# Breadboard.net
KiCad netlist of a schematic drawn in EAGLE
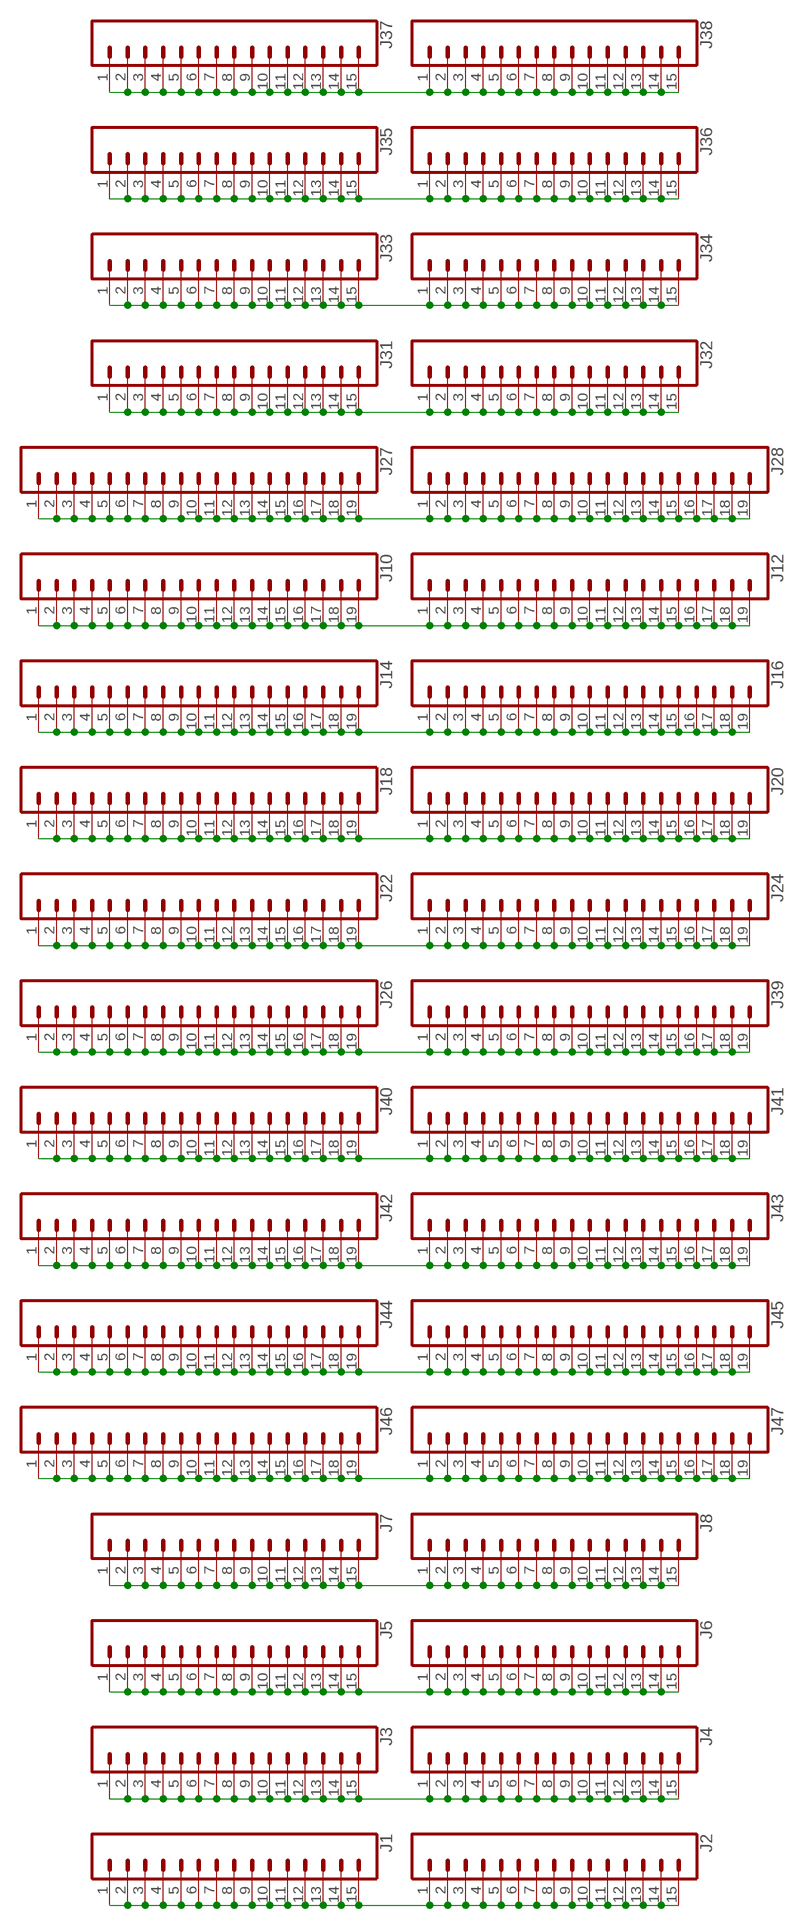
[diagram p0: schematic, sheet 1]
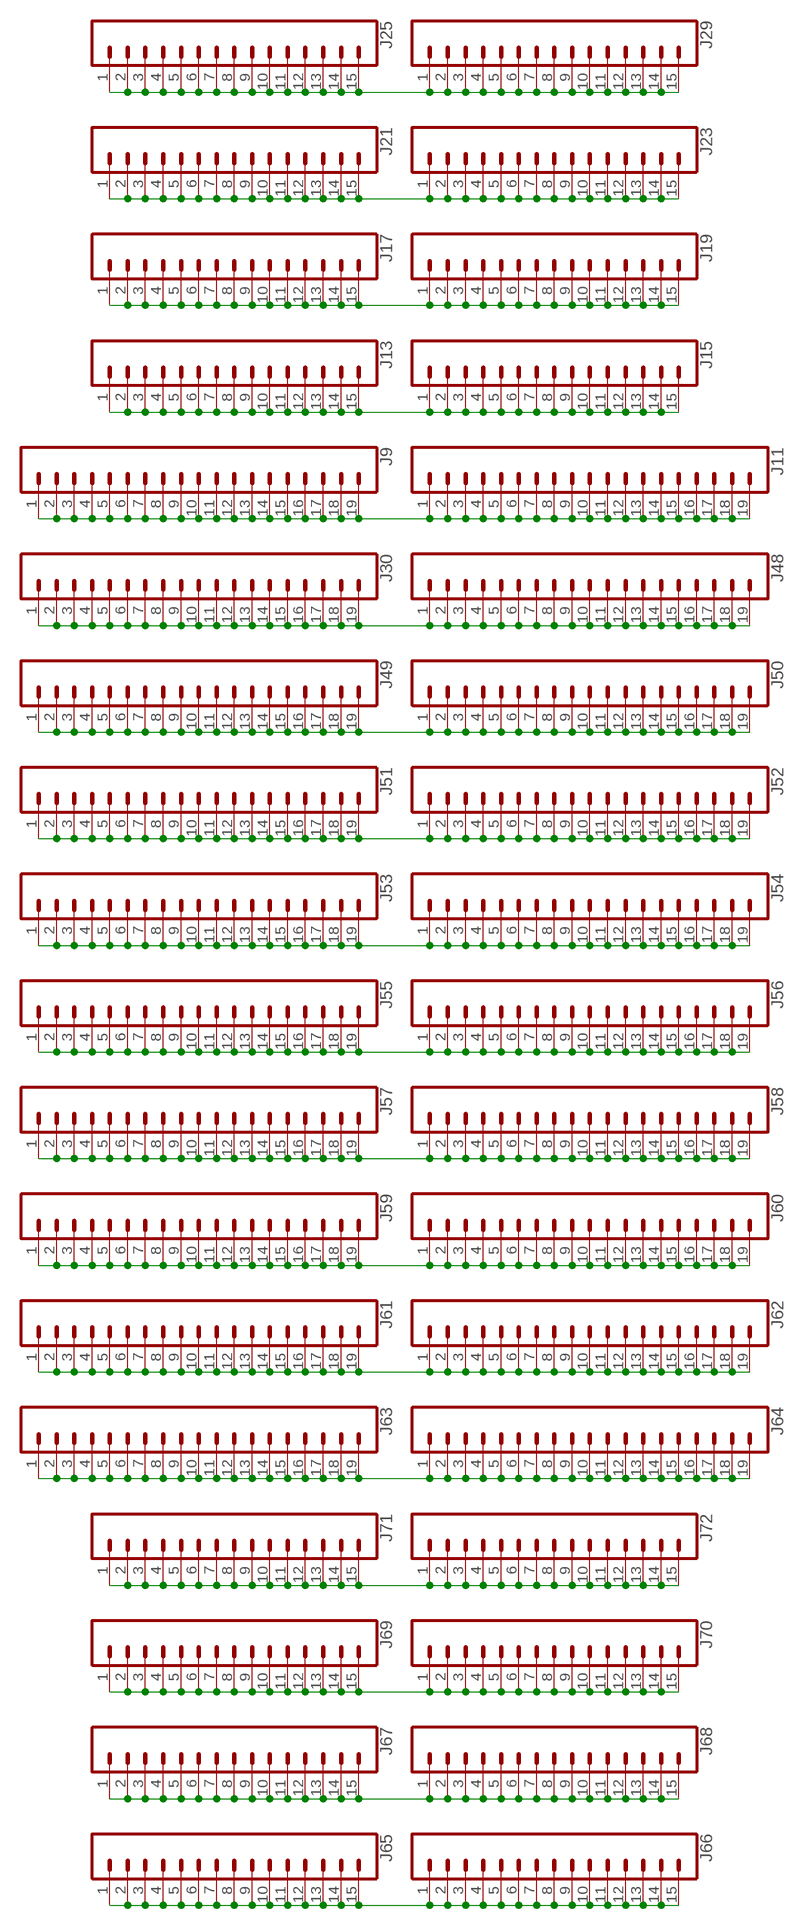
[diagram p1: schematic, sheet 2]

(export (version "E")
  (design (tool "Eeschema 10.0.6"))
  (components
    (comp (ref "J1")
      (value "CONN_15")
      (footprint "eagle-import:1X15")
      (libsource (lib "eagle-import") (part "CONN_15"))
    )
    (comp (ref "J2")
      (value "CONN_15")
      (footprint "eagle-import:1X15")
      (libsource (lib "eagle-import") (part "CONN_15"))
    )
    (comp (ref "J3")
      (value "CONN_15")
      (footprint "eagle-import:1X15")
      (libsource (lib "eagle-import") (part "CONN_15"))
    )
    (comp (ref "J4")
      (value "CONN_15")
      (footprint "eagle-import:1X15")
      (libsource (lib "eagle-import") (part "CONN_15"))
    )
    (comp (ref "J5")
      (value "CONN_15")
      (footprint "eagle-import:1X15")
      (libsource (lib "eagle-import") (part "CONN_15"))
    )
    (comp (ref "J6")
      (value "CONN_15")
      (footprint "eagle-import:1X15")
      (libsource (lib "eagle-import") (part "CONN_15"))
    )
    (comp (ref "J7")
      (value "CONN_15")
      (footprint "eagle-import:1X15")
      (libsource (lib "eagle-import") (part "CONN_15"))
    )
    (comp (ref "J8")
      (value "CONN_15")
      (footprint "eagle-import:1X15")
      (libsource (lib "eagle-import") (part "CONN_15"))
    )
    (comp (ref "J10")
      (value "CONN_19")
      (footprint "eagle-import:1X19")
      (libsource (lib "eagle-import") (part "CONN_19"))
    )
    (comp (ref "J12")
      (value "CONN_19")
      (footprint "eagle-import:1X19")
      (libsource (lib "eagle-import") (part "CONN_19"))
    )
    (comp (ref "J14")
      (value "CONN_19")
      (footprint "eagle-import:1X19")
      (libsource (lib "eagle-import") (part "CONN_19"))
    )
    (comp (ref "J16")
      (value "CONN_19")
      (footprint "eagle-import:1X19")
      (libsource (lib "eagle-import") (part "CONN_19"))
    )
    (comp (ref "J18")
      (value "CONN_19")
      (footprint "eagle-import:1X19")
      (libsource (lib "eagle-import") (part "CONN_19"))
    )
    (comp (ref "J20")
      (value "CONN_19")
      (footprint "eagle-import:1X19")
      (libsource (lib "eagle-import") (part "CONN_19"))
    )
    (comp (ref "J22")
      (value "CONN_19")
      (footprint "eagle-import:1X19")
      (libsource (lib "eagle-import") (part "CONN_19"))
    )
    (comp (ref "J24")
      (value "CONN_19")
      (footprint "eagle-import:1X19")
      (libsource (lib "eagle-import") (part "CONN_19"))
    )
    (comp (ref "J26")
      (value "CONN_19")
      (footprint "eagle-import:1X19")
      (libsource (lib "eagle-import") (part "CONN_19"))
    )
    (comp (ref "J27")
      (value "CONN_19")
      (footprint "eagle-import:1X19")
      (libsource (lib "eagle-import") (part "CONN_19"))
    )
    (comp (ref "J28")
      (value "CONN_19")
      (footprint "eagle-import:1X19")
      (libsource (lib "eagle-import") (part "CONN_19"))
    )
    (comp (ref "J31")
      (value "CONN_15")
      (footprint "eagle-import:1X15")
      (libsource (lib "eagle-import") (part "CONN_15"))
    )
    (comp (ref "J32")
      (value "CONN_15")
      (footprint "eagle-import:1X15")
      (libsource (lib "eagle-import") (part "CONN_15"))
    )
    (comp (ref "J33")
      (value "CONN_15")
      (footprint "eagle-import:1X15")
      (libsource (lib "eagle-import") (part "CONN_15"))
    )
    (comp (ref "J34")
      (value "CONN_15")
      (footprint "eagle-import:1X15")
      (libsource (lib "eagle-import") (part "CONN_15"))
    )
    (comp (ref "J35")
      (value "CONN_15")
      (footprint "eagle-import:1X15")
      (libsource (lib "eagle-import") (part "CONN_15"))
    )
    (comp (ref "J36")
      (value "CONN_15")
      (footprint "eagle-import:1X15")
      (libsource (lib "eagle-import") (part "CONN_15"))
    )
    (comp (ref "J37")
      (value "CONN_15")
      (footprint "eagle-import:1X15")
      (libsource (lib "eagle-import") (part "CONN_15"))
    )
    (comp (ref "J38")
      (value "CONN_15")
      (footprint "eagle-import:1X15")
      (libsource (lib "eagle-import") (part "CONN_15"))
    )
    (comp (ref "J39")
      (value "CONN_19")
      (footprint "eagle-import:1X19")
      (libsource (lib "eagle-import") (part "CONN_19"))
    )
    (comp (ref "J40")
      (value "CONN_19")
      (footprint "eagle-import:1X19")
      (libsource (lib "eagle-import") (part "CONN_19"))
    )
    (comp (ref "J41")
      (value "CONN_19")
      (footprint "eagle-import:1X19")
      (libsource (lib "eagle-import") (part "CONN_19"))
    )
    (comp (ref "J42")
      (value "CONN_19")
      (footprint "eagle-import:1X19")
      (libsource (lib "eagle-import") (part "CONN_19"))
    )
    (comp (ref "J43")
      (value "CONN_19")
      (footprint "eagle-import:1X19")
      (libsource (lib "eagle-import") (part "CONN_19"))
    )
    (comp (ref "J44")
      (value "CONN_19")
      (footprint "eagle-import:1X19")
      (libsource (lib "eagle-import") (part "CONN_19"))
    )
    (comp (ref "J45")
      (value "CONN_19")
      (footprint "eagle-import:1X19")
      (libsource (lib "eagle-import") (part "CONN_19"))
    )
    (comp (ref "J46")
      (value "CONN_19")
      (footprint "eagle-import:1X19")
      (libsource (lib "eagle-import") (part "CONN_19"))
    )
    (comp (ref "J47")
      (value "CONN_19")
      (footprint "eagle-import:1X19")
      (libsource (lib "eagle-import") (part "CONN_19"))
    )
    (comp (ref "J9")
      (value "CONN_19")
      (footprint "eagle-import:1X19")
      (libsource (lib "eagle-import") (part "CONN_19"))
    )
    (comp (ref "J11")
      (value "CONN_19")
      (footprint "eagle-import:1X19")
      (libsource (lib "eagle-import") (part "CONN_19"))
    )
    (comp (ref "J13")
      (value "CONN_15")
      (footprint "eagle-import:1X15")
      (libsource (lib "eagle-import") (part "CONN_15"))
    )
    (comp (ref "J15")
      (value "CONN_15")
      (footprint "eagle-import:1X15")
      (libsource (lib "eagle-import") (part "CONN_15"))
    )
    (comp (ref "J17")
      (value "CONN_15")
      (footprint "eagle-import:1X15")
      (libsource (lib "eagle-import") (part "CONN_15"))
    )
    (comp (ref "J19")
      (value "CONN_15")
      (footprint "eagle-import:1X15")
      (libsource (lib "eagle-import") (part "CONN_15"))
    )
    (comp (ref "J21")
      (value "CONN_15")
      (footprint "eagle-import:1X15")
      (libsource (lib "eagle-import") (part "CONN_15"))
    )
    (comp (ref "J23")
      (value "CONN_15")
      (footprint "eagle-import:1X15")
      (libsource (lib "eagle-import") (part "CONN_15"))
    )
    (comp (ref "J25")
      (value "CONN_15")
      (footprint "eagle-import:1X15")
      (libsource (lib "eagle-import") (part "CONN_15"))
    )
    (comp (ref "J29")
      (value "CONN_15")
      (footprint "eagle-import:1X15")
      (libsource (lib "eagle-import") (part "CONN_15"))
    )
    (comp (ref "J30")
      (value "CONN_19")
      (footprint "eagle-import:1X19")
      (libsource (lib "eagle-import") (part "CONN_19"))
    )
    (comp (ref "J48")
      (value "CONN_19")
      (footprint "eagle-import:1X19")
      (libsource (lib "eagle-import") (part "CONN_19"))
    )
    (comp (ref "J49")
      (value "CONN_19")
      (footprint "eagle-import:1X19")
      (libsource (lib "eagle-import") (part "CONN_19"))
    )
    (comp (ref "J50")
      (value "CONN_19")
      (footprint "eagle-import:1X19")
      (libsource (lib "eagle-import") (part "CONN_19"))
    )
    (comp (ref "J51")
      (value "CONN_19")
      (footprint "eagle-import:1X19")
      (libsource (lib "eagle-import") (part "CONN_19"))
    )
    (comp (ref "J52")
      (value "CONN_19")
      (footprint "eagle-import:1X19")
      (libsource (lib "eagle-import") (part "CONN_19"))
    )
    (comp (ref "J53")
      (value "CONN_19")
      (footprint "eagle-import:1X19")
      (libsource (lib "eagle-import") (part "CONN_19"))
    )
    (comp (ref "J54")
      (value "CONN_19")
      (footprint "eagle-import:1X19")
      (libsource (lib "eagle-import") (part "CONN_19"))
    )
    (comp (ref "J55")
      (value "CONN_19")
      (footprint "eagle-import:1X19")
      (libsource (lib "eagle-import") (part "CONN_19"))
    )
    (comp (ref "J56")
      (value "CONN_19")
      (footprint "eagle-import:1X19")
      (libsource (lib "eagle-import") (part "CONN_19"))
    )
    (comp (ref "J57")
      (value "CONN_19")
      (footprint "eagle-import:1X19")
      (libsource (lib "eagle-import") (part "CONN_19"))
    )
    (comp (ref "J58")
      (value "CONN_19")
      (footprint "eagle-import:1X19")
      (libsource (lib "eagle-import") (part "CONN_19"))
    )
    (comp (ref "J59")
      (value "CONN_19")
      (footprint "eagle-import:1X19")
      (libsource (lib "eagle-import") (part "CONN_19"))
    )
    (comp (ref "J60")
      (value "CONN_19")
      (footprint "eagle-import:1X19")
      (libsource (lib "eagle-import") (part "CONN_19"))
    )
    (comp (ref "J61")
      (value "CONN_19")
      (footprint "eagle-import:1X19")
      (libsource (lib "eagle-import") (part "CONN_19"))
    )
    (comp (ref "J62")
      (value "CONN_19")
      (footprint "eagle-import:1X19")
      (libsource (lib "eagle-import") (part "CONN_19"))
    )
    (comp (ref "J63")
      (value "CONN_19")
      (footprint "eagle-import:1X19")
      (libsource (lib "eagle-import") (part "CONN_19"))
    )
    (comp (ref "J64")
      (value "CONN_19")
      (footprint "eagle-import:1X19")
      (libsource (lib "eagle-import") (part "CONN_19"))
    )
    (comp (ref "J65")
      (value "CONN_15")
      (footprint "eagle-import:1X15")
      (libsource (lib "eagle-import") (part "CONN_15"))
    )
    (comp (ref "J66")
      (value "CONN_15")
      (footprint "eagle-import:1X15")
      (libsource (lib "eagle-import") (part "CONN_15"))
    )
    (comp (ref "J67")
      (value "CONN_15")
      (footprint "eagle-import:1X15")
      (libsource (lib "eagle-import") (part "CONN_15"))
    )
    (comp (ref "J68")
      (value "CONN_15")
      (footprint "eagle-import:1X15")
      (libsource (lib "eagle-import") (part "CONN_15"))
    )
    (comp (ref "J69")
      (value "CONN_15")
      (footprint "eagle-import:1X15")
      (libsource (lib "eagle-import") (part "CONN_15"))
    )
    (comp (ref "J70")
      (value "CONN_15")
      (footprint "eagle-import:1X15")
      (libsource (lib "eagle-import") (part "CONN_15"))
    )
    (comp (ref "J71")
      (value "CONN_15")
      (footprint "eagle-import:1X15")
      (libsource (lib "eagle-import") (part "CONN_15"))
    )
    (comp (ref "J72")
      (value "CONN_15")
      (footprint "eagle-import:1X15")
      (libsource (lib "eagle-import") (part "CONN_15"))
    )
  )
  (nets
    (net (code "1") (name "Net-(J1-Pad1)") (class "Default")
      (node (ref "J1") (pin "1") (pinfunction "1_1") (pintype "passive"))
      (node (ref "J1") (pin "10") (pinfunction "10_10") (pintype "passive"))
      (node (ref "J1") (pin "11") (pinfunction "11_11") (pintype "passive"))
      (node (ref "J1") (pin "12") (pinfunction "12_12") (pintype "passive"))
      (node (ref "J1") (pin "13") (pinfunction "13_13") (pintype "passive"))
      (node (ref "J1") (pin "14") (pinfunction "14_14") (pintype "passive"))
      (node (ref "J1") (pin "15") (pinfunction "15_15") (pintype "passive"))
      (node (ref "J1") (pin "2") (pinfunction "2_2") (pintype "passive"))
      (node (ref "J1") (pin "3") (pinfunction "3_3") (pintype "passive"))
      (node (ref "J1") (pin "4") (pinfunction "4_4") (pintype "passive"))
      (node (ref "J1") (pin "5") (pinfunction "5_5") (pintype "passive"))
      (node (ref "J1") (pin "6") (pinfunction "6_6") (pintype "passive"))
      (node (ref "J1") (pin "7") (pinfunction "7_7") (pintype "passive"))
      (node (ref "J1") (pin "8") (pinfunction "8_8") (pintype "passive"))
      (node (ref "J1") (pin "9") (pinfunction "9_9") (pintype "passive"))
      (node (ref "J2") (pin "1") (pinfunction "1_1") (pintype "passive"))
      (node (ref "J2") (pin "10") (pinfunction "10_10") (pintype "passive"))
      (node (ref "J2") (pin "11") (pinfunction "11_11") (pintype "passive"))
      (node (ref "J2") (pin "12") (pinfunction "12_12") (pintype "passive"))
      (node (ref "J2") (pin "13") (pinfunction "13_13") (pintype "passive"))
      (node (ref "J2") (pin "14") (pinfunction "14_14") (pintype "passive"))
      (node (ref "J2") (pin "15") (pinfunction "15_15") (pintype "passive"))
      (node (ref "J2") (pin "2") (pinfunction "2_2") (pintype "passive"))
      (node (ref "J2") (pin "3") (pinfunction "3_3") (pintype "passive"))
      (node (ref "J2") (pin "4") (pinfunction "4_4") (pintype "passive"))
      (node (ref "J2") (pin "5") (pinfunction "5_5") (pintype "passive"))
      (node (ref "J2") (pin "6") (pinfunction "6_6") (pintype "passive"))
      (node (ref "J2") (pin "7") (pinfunction "7_7") (pintype "passive"))
      (node (ref "J2") (pin "8") (pinfunction "8_8") (pintype "passive"))
      (node (ref "J2") (pin "9") (pinfunction "9_9") (pintype "passive"))
    )
    (net (code "2") (name "Net-(J3-Pad1)") (class "Default")
      (node (ref "J3") (pin "1") (pinfunction "1_1") (pintype "passive"))
      (node (ref "J3") (pin "10") (pinfunction "10_10") (pintype "passive"))
      (node (ref "J3") (pin "11") (pinfunction "11_11") (pintype "passive"))
      (node (ref "J3") (pin "12") (pinfunction "12_12") (pintype "passive"))
      (node (ref "J3") (pin "13") (pinfunction "13_13") (pintype "passive"))
      (node (ref "J3") (pin "14") (pinfunction "14_14") (pintype "passive"))
      (node (ref "J3") (pin "15") (pinfunction "15_15") (pintype "passive"))
      (node (ref "J3") (pin "2") (pinfunction "2_2") (pintype "passive"))
      (node (ref "J3") (pin "3") (pinfunction "3_3") (pintype "passive"))
      (node (ref "J3") (pin "4") (pinfunction "4_4") (pintype "passive"))
      (node (ref "J3") (pin "5") (pinfunction "5_5") (pintype "passive"))
      (node (ref "J3") (pin "6") (pinfunction "6_6") (pintype "passive"))
      (node (ref "J3") (pin "7") (pinfunction "7_7") (pintype "passive"))
      (node (ref "J3") (pin "8") (pinfunction "8_8") (pintype "passive"))
      (node (ref "J3") (pin "9") (pinfunction "9_9") (pintype "passive"))
      (node (ref "J4") (pin "1") (pinfunction "1_1") (pintype "passive"))
      (node (ref "J4") (pin "10") (pinfunction "10_10") (pintype "passive"))
      (node (ref "J4") (pin "11") (pinfunction "11_11") (pintype "passive"))
      (node (ref "J4") (pin "12") (pinfunction "12_12") (pintype "passive"))
      (node (ref "J4") (pin "13") (pinfunction "13_13") (pintype "passive"))
      (node (ref "J4") (pin "14") (pinfunction "14_14") (pintype "passive"))
      (node (ref "J4") (pin "15") (pinfunction "15_15") (pintype "passive"))
      (node (ref "J4") (pin "2") (pinfunction "2_2") (pintype "passive"))
      (node (ref "J4") (pin "3") (pinfunction "3_3") (pintype "passive"))
      (node (ref "J4") (pin "4") (pinfunction "4_4") (pintype "passive"))
      (node (ref "J4") (pin "5") (pinfunction "5_5") (pintype "passive"))
      (node (ref "J4") (pin "6") (pinfunction "6_6") (pintype "passive"))
      (node (ref "J4") (pin "7") (pinfunction "7_7") (pintype "passive"))
      (node (ref "J4") (pin "8") (pinfunction "8_8") (pintype "passive"))
      (node (ref "J4") (pin "9") (pinfunction "9_9") (pintype "passive"))
    )
    (net (code "3") (name "Net-(J5-Pad1)") (class "Default")
      (node (ref "J5") (pin "1") (pinfunction "1_1") (pintype "passive"))
      (node (ref "J5") (pin "10") (pinfunction "10_10") (pintype "passive"))
      (node (ref "J5") (pin "11") (pinfunction "11_11") (pintype "passive"))
      (node (ref "J5") (pin "12") (pinfunction "12_12") (pintype "passive"))
      (node (ref "J5") (pin "13") (pinfunction "13_13") (pintype "passive"))
      (node (ref "J5") (pin "14") (pinfunction "14_14") (pintype "passive"))
      (node (ref "J5") (pin "15") (pinfunction "15_15") (pintype "passive"))
      (node (ref "J5") (pin "2") (pinfunction "2_2") (pintype "passive"))
      (node (ref "J5") (pin "3") (pinfunction "3_3") (pintype "passive"))
      (node (ref "J5") (pin "4") (pinfunction "4_4") (pintype "passive"))
      (node (ref "J5") (pin "5") (pinfunction "5_5") (pintype "passive"))
      (node (ref "J5") (pin "6") (pinfunction "6_6") (pintype "passive"))
      (node (ref "J5") (pin "7") (pinfunction "7_7") (pintype "passive"))
      (node (ref "J5") (pin "8") (pinfunction "8_8") (pintype "passive"))
      (node (ref "J5") (pin "9") (pinfunction "9_9") (pintype "passive"))
      (node (ref "J6") (pin "1") (pinfunction "1_1") (pintype "passive"))
      (node (ref "J6") (pin "10") (pinfunction "10_10") (pintype "passive"))
      (node (ref "J6") (pin "11") (pinfunction "11_11") (pintype "passive"))
      (node (ref "J6") (pin "12") (pinfunction "12_12") (pintype "passive"))
      (node (ref "J6") (pin "13") (pinfunction "13_13") (pintype "passive"))
      (node (ref "J6") (pin "14") (pinfunction "14_14") (pintype "passive"))
      (node (ref "J6") (pin "15") (pinfunction "15_15") (pintype "passive"))
      (node (ref "J6") (pin "2") (pinfunction "2_2") (pintype "passive"))
      (node (ref "J6") (pin "3") (pinfunction "3_3") (pintype "passive"))
      (node (ref "J6") (pin "4") (pinfunction "4_4") (pintype "passive"))
      (node (ref "J6") (pin "5") (pinfunction "5_5") (pintype "passive"))
      (node (ref "J6") (pin "6") (pinfunction "6_6") (pintype "passive"))
      (node (ref "J6") (pin "7") (pinfunction "7_7") (pintype "passive"))
      (node (ref "J6") (pin "8") (pinfunction "8_8") (pintype "passive"))
      (node (ref "J6") (pin "9") (pinfunction "9_9") (pintype "passive"))
    )
    (net (code "4") (name "Net-(J7-Pad1)") (class "Default")
      (node (ref "J7") (pin "1") (pinfunction "1_1") (pintype "passive"))
      (node (ref "J7") (pin "10") (pinfunction "10_10") (pintype "passive"))
      (node (ref "J7") (pin "11") (pinfunction "11_11") (pintype "passive"))
      (node (ref "J7") (pin "12") (pinfunction "12_12") (pintype "passive"))
      (node (ref "J7") (pin "13") (pinfunction "13_13") (pintype "passive"))
      (node (ref "J7") (pin "14") (pinfunction "14_14") (pintype "passive"))
      (node (ref "J7") (pin "15") (pinfunction "15_15") (pintype "passive"))
      (node (ref "J7") (pin "2") (pinfunction "2_2") (pintype "passive"))
      (node (ref "J7") (pin "3") (pinfunction "3_3") (pintype "passive"))
      (node (ref "J7") (pin "4") (pinfunction "4_4") (pintype "passive"))
      (node (ref "J7") (pin "5") (pinfunction "5_5") (pintype "passive"))
      (node (ref "J7") (pin "6") (pinfunction "6_6") (pintype "passive"))
      (node (ref "J7") (pin "7") (pinfunction "7_7") (pintype "passive"))
      (node (ref "J7") (pin "8") (pinfunction "8_8") (pintype "passive"))
      (node (ref "J7") (pin "9") (pinfunction "9_9") (pintype "passive"))
      (node (ref "J8") (pin "1") (pinfunction "1_1") (pintype "passive"))
      (node (ref "J8") (pin "10") (pinfunction "10_10") (pintype "passive"))
      (node (ref "J8") (pin "11") (pinfunction "11_11") (pintype "passive"))
      (node (ref "J8") (pin "12") (pinfunction "12_12") (pintype "passive"))
      (node (ref "J8") (pin "13") (pinfunction "13_13") (pintype "passive"))
      (node (ref "J8") (pin "14") (pinfunction "14_14") (pintype "passive"))
      (node (ref "J8") (pin "15") (pinfunction "15_15") (pintype "passive"))
      (node (ref "J8") (pin "2") (pinfunction "2_2") (pintype "passive"))
      (node (ref "J8") (pin "3") (pinfunction "3_3") (pintype "passive"))
      (node (ref "J8") (pin "4") (pinfunction "4_4") (pintype "passive"))
      (node (ref "J8") (pin "5") (pinfunction "5_5") (pintype "passive"))
      (node (ref "J8") (pin "6") (pinfunction "6_6") (pintype "passive"))
      (node (ref "J8") (pin "7") (pinfunction "7_7") (pintype "passive"))
      (node (ref "J8") (pin "8") (pinfunction "8_8") (pintype "passive"))
      (node (ref "J8") (pin "9") (pinfunction "9_9") (pintype "passive"))
    )
    (net (code "5") (name "Net-(J10-Pad1)") (class "Default")
      (node (ref "J10") (pin "1") (pinfunction "1_1") (pintype "passive"))
      (node (ref "J10") (pin "10") (pinfunction "10_10") (pintype "passive"))
      (node (ref "J10") (pin "11") (pinfunction "11_11") (pintype "passive"))
      (node (ref "J10") (pin "12") (pinfunction "12_12") (pintype "passive"))
      (node (ref "J10") (pin "13") (pinfunction "13_13") (pintype "passive"))
      (node (ref "J10") (pin "14") (pinfunction "14_14") (pintype "passive"))
      (node (ref "J10") (pin "15") (pinfunction "15_15") (pintype "passive"))
      (node (ref "J10") (pin "16") (pinfunction "16_16") (pintype "passive"))
      (node (ref "J10") (pin "17") (pinfunction "17_17") (pintype "passive"))
      (node (ref "J10") (pin "18") (pinfunction "18_18") (pintype "passive"))
      (node (ref "J10") (pin "19") (pinfunction "19_19") (pintype "passive"))
      (node (ref "J10") (pin "2") (pinfunction "2_2") (pintype "passive"))
      (node (ref "J10") (pin "3") (pinfunction "3_3") (pintype "passive"))
      (node (ref "J10") (pin "4") (pinfunction "4_4") (pintype "passive"))
      (node (ref "J10") (pin "5") (pinfunction "5_5") (pintype "passive"))
      (node (ref "J10") (pin "6") (pinfunction "6_6") (pintype "passive"))
      (node (ref "J10") (pin "7") (pinfunction "7_7") (pintype "passive"))
      (node (ref "J10") (pin "8") (pinfunction "8_8") (pintype "passive"))
      (node (ref "J10") (pin "9") (pinfunction "9_9") (pintype "passive"))
      (node (ref "J12") (pin "1") (pinfunction "1_1") (pintype "passive"))
      (node (ref "J12") (pin "10") (pinfunction "10_10") (pintype "passive"))
      (node (ref "J12") (pin "11") (pinfunction "11_11") (pintype "passive"))
      (node (ref "J12") (pin "12") (pinfunction "12_12") (pintype "passive"))
      (node (ref "J12") (pin "13") (pinfunction "13_13") (pintype "passive"))
      (node (ref "J12") (pin "14") (pinfunction "14_14") (pintype "passive"))
      (node (ref "J12") (pin "15") (pinfunction "15_15") (pintype "passive"))
      (node (ref "J12") (pin "16") (pinfunction "16_16") (pintype "passive"))
      (node (ref "J12") (pin "17") (pinfunction "17_17") (pintype "passive"))
      (node (ref "J12") (pin "18") (pinfunction "18_18") (pintype "passive"))
      (node (ref "J12") (pin "19") (pinfunction "19_19") (pintype "passive"))
      (node (ref "J12") (pin "2") (pinfunction "2_2") (pintype "passive"))
      (node (ref "J12") (pin "3") (pinfunction "3_3") (pintype "passive"))
      (node (ref "J12") (pin "4") (pinfunction "4_4") (pintype "passive"))
      (node (ref "J12") (pin "5") (pinfunction "5_5") (pintype "passive"))
      (node (ref "J12") (pin "6") (pinfunction "6_6") (pintype "passive"))
      (node (ref "J12") (pin "7") (pinfunction "7_7") (pintype "passive"))
      (node (ref "J12") (pin "8") (pinfunction "8_8") (pintype "passive"))
      (node (ref "J12") (pin "9") (pinfunction "9_9") (pintype "passive"))
    )
    (net (code "6") (name "Net-(J11-Pad1)") (class "Default")
      (node (ref "J11") (pin "1") (pinfunction "1_1") (pintype "passive"))
      (node (ref "J11") (pin "10") (pinfunction "10_10") (pintype "passive"))
      (node (ref "J11") (pin "11") (pinfunction "11_11") (pintype "passive"))
      (node (ref "J11") (pin "12") (pinfunction "12_12") (pintype "passive"))
      (node (ref "J11") (pin "13") (pinfunction "13_13") (pintype "passive"))
      (node (ref "J11") (pin "14") (pinfunction "14_14") (pintype "passive"))
      (node (ref "J11") (pin "15") (pinfunction "15_15") (pintype "passive"))
      (node (ref "J11") (pin "16") (pinfunction "16_16") (pintype "passive"))
      (node (ref "J11") (pin "17") (pinfunction "17_17") (pintype "passive"))
      (node (ref "J11") (pin "18") (pinfunction "18_18") (pintype "passive"))
      (node (ref "J11") (pin "19") (pinfunction "19_19") (pintype "passive"))
      (node (ref "J11") (pin "2") (pinfunction "2_2") (pintype "passive"))
      (node (ref "J11") (pin "3") (pinfunction "3_3") (pintype "passive"))
      (node (ref "J11") (pin "4") (pinfunction "4_4") (pintype "passive"))
      (node (ref "J11") (pin "5") (pinfunction "5_5") (pintype "passive"))
      (node (ref "J11") (pin "6") (pinfunction "6_6") (pintype "passive"))
      (node (ref "J11") (pin "7") (pinfunction "7_7") (pintype "passive"))
      (node (ref "J11") (pin "8") (pinfunction "8_8") (pintype "passive"))
      (node (ref "J11") (pin "9") (pinfunction "9_9") (pintype "passive"))
      (node (ref "J9") (pin "1") (pinfunction "1_1") (pintype "passive"))
      (node (ref "J9") (pin "10") (pinfunction "10_10") (pintype "passive"))
      (node (ref "J9") (pin "11") (pinfunction "11_11") (pintype "passive"))
      (node (ref "J9") (pin "12") (pinfunction "12_12") (pintype "passive"))
      (node (ref "J9") (pin "13") (pinfunction "13_13") (pintype "passive"))
      (node (ref "J9") (pin "14") (pinfunction "14_14") (pintype "passive"))
      (node (ref "J9") (pin "15") (pinfunction "15_15") (pintype "passive"))
      (node (ref "J9") (pin "16") (pinfunction "16_16") (pintype "passive"))
      (node (ref "J9") (pin "17") (pinfunction "17_17") (pintype "passive"))
      (node (ref "J9") (pin "18") (pinfunction "18_18") (pintype "passive"))
      (node (ref "J9") (pin "19") (pinfunction "19_19") (pintype "passive"))
      (node (ref "J9") (pin "2") (pinfunction "2_2") (pintype "passive"))
      (node (ref "J9") (pin "3") (pinfunction "3_3") (pintype "passive"))
      (node (ref "J9") (pin "4") (pinfunction "4_4") (pintype "passive"))
      (node (ref "J9") (pin "5") (pinfunction "5_5") (pintype "passive"))
      (node (ref "J9") (pin "6") (pinfunction "6_6") (pintype "passive"))
      (node (ref "J9") (pin "7") (pinfunction "7_7") (pintype "passive"))
      (node (ref "J9") (pin "8") (pinfunction "8_8") (pintype "passive"))
      (node (ref "J9") (pin "9") (pinfunction "9_9") (pintype "passive"))
    )
    (net (code "7") (name "Net-(J13-Pad1)") (class "Default")
      (node (ref "J13") (pin "1") (pinfunction "1_1") (pintype "passive"))
      (node (ref "J13") (pin "10") (pinfunction "10_10") (pintype "passive"))
      (node (ref "J13") (pin "11") (pinfunction "11_11") (pintype "passive"))
      (node (ref "J13") (pin "12") (pinfunction "12_12") (pintype "passive"))
      (node (ref "J13") (pin "13") (pinfunction "13_13") (pintype "passive"))
      (node (ref "J13") (pin "14") (pinfunction "14_14") (pintype "passive"))
      (node (ref "J13") (pin "15") (pinfunction "15_15") (pintype "passive"))
      (node (ref "J13") (pin "2") (pinfunction "2_2") (pintype "passive"))
      (node (ref "J13") (pin "3") (pinfunction "3_3") (pintype "passive"))
      (node (ref "J13") (pin "4") (pinfunction "4_4") (pintype "passive"))
      (node (ref "J13") (pin "5") (pinfunction "5_5") (pintype "passive"))
      (node (ref "J13") (pin "6") (pinfunction "6_6") (pintype "passive"))
      (node (ref "J13") (pin "7") (pinfunction "7_7") (pintype "passive"))
      (node (ref "J13") (pin "8") (pinfunction "8_8") (pintype "passive"))
      (node (ref "J13") (pin "9") (pinfunction "9_9") (pintype "passive"))
      (node (ref "J15") (pin "1") (pinfunction "1_1") (pintype "passive"))
      (node (ref "J15") (pin "10") (pinfunction "10_10") (pintype "passive"))
      (node (ref "J15") (pin "11") (pinfunction "11_11") (pintype "passive"))
      (node (ref "J15") (pin "12") (pinfunction "12_12") (pintype "passive"))
      (node (ref "J15") (pin "13") (pinfunction "13_13") (pintype "passive"))
      (node (ref "J15") (pin "14") (pinfunction "14_14") (pintype "passive"))
      (node (ref "J15") (pin "15") (pinfunction "15_15") (pintype "passive"))
      (node (ref "J15") (pin "2") (pinfunction "2_2") (pintype "passive"))
      (node (ref "J15") (pin "3") (pinfunction "3_3") (pintype "passive"))
      (node (ref "J15") (pin "4") (pinfunction "4_4") (pintype "passive"))
      (node (ref "J15") (pin "5") (pinfunction "5_5") (pintype "passive"))
      (node (ref "J15") (pin "6") (pinfunction "6_6") (pintype "passive"))
      (node (ref "J15") (pin "7") (pinfunction "7_7") (pintype "passive"))
      (node (ref "J15") (pin "8") (pinfunction "8_8") (pintype "passive"))
      (node (ref "J15") (pin "9") (pinfunction "9_9") (pintype "passive"))
    )
    (net (code "8") (name "Net-(J14-Pad1)") (class "Default")
      (node (ref "J14") (pin "1") (pinfunction "1_1") (pintype "passive"))
      (node (ref "J14") (pin "10") (pinfunction "10_10") (pintype "passive"))
      (node (ref "J14") (pin "11") (pinfunction "11_11") (pintype "passive"))
      (node (ref "J14") (pin "12") (pinfunction "12_12") (pintype "passive"))
      (node (ref "J14") (pin "13") (pinfunction "13_13") (pintype "passive"))
      (node (ref "J14") (pin "14") (pinfunction "14_14") (pintype "passive"))
      (node (ref "J14") (pin "15") (pinfunction "15_15") (pintype "passive"))
      (node (ref "J14") (pin "16") (pinfunction "16_16") (pintype "passive"))
      (node (ref "J14") (pin "17") (pinfunction "17_17") (pintype "passive"))
      (node (ref "J14") (pin "18") (pinfunction "18_18") (pintype "passive"))
      (node (ref "J14") (pin "19") (pinfunction "19_19") (pintype "passive"))
      (node (ref "J14") (pin "2") (pinfunction "2_2") (pintype "passive"))
      (node (ref "J14") (pin "3") (pinfunction "3_3") (pintype "passive"))
      (node (ref "J14") (pin "4") (pinfunction "4_4") (pintype "passive"))
      (node (ref "J14") (pin "5") (pinfunction "5_5") (pintype "passive"))
      (node (ref "J14") (pin "6") (pinfunction "6_6") (pintype "passive"))
      (node (ref "J14") (pin "7") (pinfunction "7_7") (pintype "passive"))
      (node (ref "J14") (pin "8") (pinfunction "8_8") (pintype "passive"))
      (node (ref "J14") (pin "9") (pinfunction "9_9") (pintype "passive"))
      (node (ref "J16") (pin "1") (pinfunction "1_1") (pintype "passive"))
      (node (ref "J16") (pin "10") (pinfunction "10_10") (pintype "passive"))
      (node (ref "J16") (pin "11") (pinfunction "11_11") (pintype "passive"))
      (node (ref "J16") (pin "12") (pinfunction "12_12") (pintype "passive"))
      (node (ref "J16") (pin "13") (pinfunction "13_13") (pintype "passive"))
      (node (ref "J16") (pin "14") (pinfunction "14_14") (pintype "passive"))
      (node (ref "J16") (pin "15") (pinfunction "15_15") (pintype "passive"))
      (node (ref "J16") (pin "16") (pinfunction "16_16") (pintype "passive"))
      (node (ref "J16") (pin "17") (pinfunction "17_17") (pintype "passive"))
      (node (ref "J16") (pin "18") (pinfunction "18_18") (pintype "passive"))
      (node (ref "J16") (pin "19") (pinfunction "19_19") (pintype "passive"))
      (node (ref "J16") (pin "2") (pinfunction "2_2") (pintype "passive"))
      (node (ref "J16") (pin "3") (pinfunction "3_3") (pintype "passive"))
      (node (ref "J16") (pin "4") (pinfunction "4_4") (pintype "passive"))
      (node (ref "J16") (pin "5") (pinfunction "5_5") (pintype "passive"))
      (node (ref "J16") (pin "6") (pinfunction "6_6") (pintype "passive"))
      (node (ref "J16") (pin "7") (pinfunction "7_7") (pintype "passive"))
      (node (ref "J16") (pin "8") (pinfunction "8_8") (pintype "passive"))
      (node (ref "J16") (pin "9") (pinfunction "9_9") (pintype "passive"))
    )
    (net (code "9") (name "Net-(J17-Pad1)") (class "Default")
      (node (ref "J17") (pin "1") (pinfunction "1_1") (pintype "passive"))
      (node (ref "J17") (pin "10") (pinfunction "10_10") (pintype "passive"))
      (node (ref "J17") (pin "11") (pinfunction "11_11") (pintype "passive"))
      (node (ref "J17") (pin "12") (pinfunction "12_12") (pintype "passive"))
      (node (ref "J17") (pin "13") (pinfunction "13_13") (pintype "passive"))
      (node (ref "J17") (pin "14") (pinfunction "14_14") (pintype "passive"))
      (node (ref "J17") (pin "15") (pinfunction "15_15") (pintype "passive"))
      (node (ref "J17") (pin "2") (pinfunction "2_2") (pintype "passive"))
      (node (ref "J17") (pin "3") (pinfunction "3_3") (pintype "passive"))
      (node (ref "J17") (pin "4") (pinfunction "4_4") (pintype "passive"))
      (node (ref "J17") (pin "5") (pinfunction "5_5") (pintype "passive"))
      (node (ref "J17") (pin "6") (pinfunction "6_6") (pintype "passive"))
      (node (ref "J17") (pin "7") (pinfunction "7_7") (pintype "passive"))
      (node (ref "J17") (pin "8") (pinfunction "8_8") (pintype "passive"))
      (node (ref "J17") (pin "9") (pinfunction "9_9") (pintype "passive"))
      (node (ref "J19") (pin "1") (pinfunction "1_1") (pintype "passive"))
      (node (ref "J19") (pin "10") (pinfunction "10_10") (pintype "passive"))
      (node (ref "J19") (pin "11") (pinfunction "11_11") (pintype "passive"))
      (node (ref "J19") (pin "12") (pinfunction "12_12") (pintype "passive"))
      (node (ref "J19") (pin "13") (pinfunction "13_13") (pintype "passive"))
      (node (ref "J19") (pin "14") (pinfunction "14_14") (pintype "passive"))
      (node (ref "J19") (pin "15") (pinfunction "15_15") (pintype "passive"))
      (node (ref "J19") (pin "2") (pinfunction "2_2") (pintype "passive"))
      (node (ref "J19") (pin "3") (pinfunction "3_3") (pintype "passive"))
      (node (ref "J19") (pin "4") (pinfunction "4_4") (pintype "passive"))
      (node (ref "J19") (pin "5") (pinfunction "5_5") (pintype "passive"))
      (node (ref "J19") (pin "6") (pinfunction "6_6") (pintype "passive"))
      (node (ref "J19") (pin "7") (pinfunction "7_7") (pintype "passive"))
      (node (ref "J19") (pin "8") (pinfunction "8_8") (pintype "passive"))
      (node (ref "J19") (pin "9") (pinfunction "9_9") (pintype "passive"))
    )
    (net (code "10") (name "Net-(J18-Pad1)") (class "Default")
      (node (ref "J18") (pin "1") (pinfunction "1_1") (pintype "passive"))
      (node (ref "J18") (pin "10") (pinfunction "10_10") (pintype "passive"))
      (node (ref "J18") (pin "11") (pinfunction "11_11") (pintype "passive"))
      (node (ref "J18") (pin "12") (pinfunction "12_12") (pintype "passive"))
      (node (ref "J18") (pin "13") (pinfunction "13_13") (pintype "passive"))
      (node (ref "J18") (pin "14") (pinfunction "14_14") (pintype "passive"))
      (node (ref "J18") (pin "15") (pinfunction "15_15") (pintype "passive"))
      (node (ref "J18") (pin "16") (pinfunction "16_16") (pintype "passive"))
      (node (ref "J18") (pin "17") (pinfunction "17_17") (pintype "passive"))
      (node (ref "J18") (pin "18") (pinfunction "18_18") (pintype "passive"))
      (node (ref "J18") (pin "19") (pinfunction "19_19") (pintype "passive"))
      (node (ref "J18") (pin "2") (pinfunction "2_2") (pintype "passive"))
      (node (ref "J18") (pin "3") (pinfunction "3_3") (pintype "passive"))
      (node (ref "J18") (pin "4") (pinfunction "4_4") (pintype "passive"))
      (node (ref "J18") (pin "5") (pinfunction "5_5") (pintype "passive"))
      (node (ref "J18") (pin "6") (pinfunction "6_6") (pintype "passive"))
      (node (ref "J18") (pin "7") (pinfunction "7_7") (pintype "passive"))
      (node (ref "J18") (pin "8") (pinfunction "8_8") (pintype "passive"))
      (node (ref "J18") (pin "9") (pinfunction "9_9") (pintype "passive"))
      (node (ref "J20") (pin "1") (pinfunction "1_1") (pintype "passive"))
      (node (ref "J20") (pin "10") (pinfunction "10_10") (pintype "passive"))
      (node (ref "J20") (pin "11") (pinfunction "11_11") (pintype "passive"))
      (node (ref "J20") (pin "12") (pinfunction "12_12") (pintype "passive"))
      (node (ref "J20") (pin "13") (pinfunction "13_13") (pintype "passive"))
      (node (ref "J20") (pin "14") (pinfunction "14_14") (pintype "passive"))
      (node (ref "J20") (pin "15") (pinfunction "15_15") (pintype "passive"))
      (node (ref "J20") (pin "16") (pinfunction "16_16") (pintype "passive"))
      (node (ref "J20") (pin "17") (pinfunction "17_17") (pintype "passive"))
      (node (ref "J20") (pin "18") (pinfunction "18_18") (pintype "passive"))
      (node (ref "J20") (pin "19") (pinfunction "19_19") (pintype "passive"))
      (node (ref "J20") (pin "2") (pinfunction "2_2") (pintype "passive"))
      (node (ref "J20") (pin "3") (pinfunction "3_3") (pintype "passive"))
      (node (ref "J20") (pin "4") (pinfunction "4_4") (pintype "passive"))
      (node (ref "J20") (pin "5") (pinfunction "5_5") (pintype "passive"))
      (node (ref "J20") (pin "6") (pinfunction "6_6") (pintype "passive"))
      (node (ref "J20") (pin "7") (pinfunction "7_7") (pintype "passive"))
      (node (ref "J20") (pin "8") (pinfunction "8_8") (pintype "passive"))
      (node (ref "J20") (pin "9") (pinfunction "9_9") (pintype "passive"))
    )
    (net (code "11") (name "Net-(J21-Pad1)") (class "Default")
      (node (ref "J21") (pin "1") (pinfunction "1_1") (pintype "passive"))
      (node (ref "J21") (pin "10") (pinfunction "10_10") (pintype "passive"))
      (node (ref "J21") (pin "11") (pinfunction "11_11") (pintype "passive"))
      (node (ref "J21") (pin "12") (pinfunction "12_12") (pintype "passive"))
      (node (ref "J21") (pin "13") (pinfunction "13_13") (pintype "passive"))
      (node (ref "J21") (pin "14") (pinfunction "14_14") (pintype "passive"))
      (node (ref "J21") (pin "15") (pinfunction "15_15") (pintype "passive"))
      (node (ref "J21") (pin "2") (pinfunction "2_2") (pintype "passive"))
      (node (ref "J21") (pin "3") (pinfunction "3_3") (pintype "passive"))
      (node (ref "J21") (pin "4") (pinfunction "4_4") (pintype "passive"))
      (node (ref "J21") (pin "5") (pinfunction "5_5") (pintype "passive"))
      (node (ref "J21") (pin "6") (pinfunction "6_6") (pintype "passive"))
      (node (ref "J21") (pin "7") (pinfunction "7_7") (pintype "passive"))
      (node (ref "J21") (pin "8") (pinfunction "8_8") (pintype "passive"))
      (node (ref "J21") (pin "9") (pinfunction "9_9") (pintype "passive"))
      (node (ref "J23") (pin "1") (pinfunction "1_1") (pintype "passive"))
      (node (ref "J23") (pin "10") (pinfunction "10_10") (pintype "passive"))
      (node (ref "J23") (pin "11") (pinfunction "11_11") (pintype "passive"))
      (node (ref "J23") (pin "12") (pinfunction "12_12") (pintype "passive"))
      (node (ref "J23") (pin "13") (pinfunction "13_13") (pintype "passive"))
      (node (ref "J23") (pin "14") (pinfunction "14_14") (pintype "passive"))
      (node (ref "J23") (pin "15") (pinfunction "15_15") (pintype "passive"))
      (node (ref "J23") (pin "2") (pinfunction "2_2") (pintype "passive"))
      (node (ref "J23") (pin "3") (pinfunction "3_3") (pintype "passive"))
      (node (ref "J23") (pin "4") (pinfunction "4_4") (pintype "passive"))
      (node (ref "J23") (pin "5") (pinfunction "5_5") (pintype "passive"))
      (node (ref "J23") (pin "6") (pinfunction "6_6") (pintype "passive"))
      (node (ref "J23") (pin "7") (pinfunction "7_7") (pintype "passive"))
      (node (ref "J23") (pin "8") (pinfunction "8_8") (pintype "passive"))
      (node (ref "J23") (pin "9") (pinfunction "9_9") (pintype "passive"))
    )
    (net (code "12") (name "Net-(J22-Pad1)") (class "Default")
      (node (ref "J22") (pin "1") (pinfunction "1_1") (pintype "passive"))
      (node (ref "J22") (pin "10") (pinfunction "10_10") (pintype "passive"))
      (node (ref "J22") (pin "11") (pinfunction "11_11") (pintype "passive"))
      (node (ref "J22") (pin "12") (pinfunction "12_12") (pintype "passive"))
      (node (ref "J22") (pin "13") (pinfunction "13_13") (pintype "passive"))
      (node (ref "J22") (pin "14") (pinfunction "14_14") (pintype "passive"))
      (node (ref "J22") (pin "15") (pinfunction "15_15") (pintype "passive"))
      (node (ref "J22") (pin "16") (pinfunction "16_16") (pintype "passive"))
      (node (ref "J22") (pin "17") (pinfunction "17_17") (pintype "passive"))
      (node (ref "J22") (pin "18") (pinfunction "18_18") (pintype "passive"))
      (node (ref "J22") (pin "19") (pinfunction "19_19") (pintype "passive"))
      (node (ref "J22") (pin "2") (pinfunction "2_2") (pintype "passive"))
      (node (ref "J22") (pin "3") (pinfunction "3_3") (pintype "passive"))
      (node (ref "J22") (pin "4") (pinfunction "4_4") (pintype "passive"))
      (node (ref "J22") (pin "5") (pinfunction "5_5") (pintype "passive"))
      (node (ref "J22") (pin "6") (pinfunction "6_6") (pintype "passive"))
      (node (ref "J22") (pin "7") (pinfunction "7_7") (pintype "passive"))
      (node (ref "J22") (pin "8") (pinfunction "8_8") (pintype "passive"))
      (node (ref "J22") (pin "9") (pinfunction "9_9") (pintype "passive"))
      (node (ref "J24") (pin "1") (pinfunction "1_1") (pintype "passive"))
      (node (ref "J24") (pin "10") (pinfunction "10_10") (pintype "passive"))
      (node (ref "J24") (pin "11") (pinfunction "11_11") (pintype "passive"))
      (node (ref "J24") (pin "12") (pinfunction "12_12") (pintype "passive"))
      (node (ref "J24") (pin "13") (pinfunction "13_13") (pintype "passive"))
      (node (ref "J24") (pin "14") (pinfunction "14_14") (pintype "passive"))
      (node (ref "J24") (pin "15") (pinfunction "15_15") (pintype "passive"))
      (node (ref "J24") (pin "16") (pinfunction "16_16") (pintype "passive"))
      (node (ref "J24") (pin "17") (pinfunction "17_17") (pintype "passive"))
      (node (ref "J24") (pin "18") (pinfunction "18_18") (pintype "passive"))
      (node (ref "J24") (pin "19") (pinfunction "19_19") (pintype "passive"))
      (node (ref "J24") (pin "2") (pinfunction "2_2") (pintype "passive"))
      (node (ref "J24") (pin "3") (pinfunction "3_3") (pintype "passive"))
      (node (ref "J24") (pin "4") (pinfunction "4_4") (pintype "passive"))
      (node (ref "J24") (pin "5") (pinfunction "5_5") (pintype "passive"))
      (node (ref "J24") (pin "6") (pinfunction "6_6") (pintype "passive"))
      (node (ref "J24") (pin "7") (pinfunction "7_7") (pintype "passive"))
      (node (ref "J24") (pin "8") (pinfunction "8_8") (pintype "passive"))
      (node (ref "J24") (pin "9") (pinfunction "9_9") (pintype "passive"))
    )
    (net (code "13") (name "Net-(J25-Pad1)") (class "Default")
      (node (ref "J25") (pin "1") (pinfunction "1_1") (pintype "passive"))
      (node (ref "J25") (pin "10") (pinfunction "10_10") (pintype "passive"))
      (node (ref "J25") (pin "11") (pinfunction "11_11") (pintype "passive"))
      (node (ref "J25") (pin "12") (pinfunction "12_12") (pintype "passive"))
      (node (ref "J25") (pin "13") (pinfunction "13_13") (pintype "passive"))
      (node (ref "J25") (pin "14") (pinfunction "14_14") (pintype "passive"))
      (node (ref "J25") (pin "15") (pinfunction "15_15") (pintype "passive"))
      (node (ref "J25") (pin "2") (pinfunction "2_2") (pintype "passive"))
      (node (ref "J25") (pin "3") (pinfunction "3_3") (pintype "passive"))
      (node (ref "J25") (pin "4") (pinfunction "4_4") (pintype "passive"))
      (node (ref "J25") (pin "5") (pinfunction "5_5") (pintype "passive"))
      (node (ref "J25") (pin "6") (pinfunction "6_6") (pintype "passive"))
      (node (ref "J25") (pin "7") (pinfunction "7_7") (pintype "passive"))
      (node (ref "J25") (pin "8") (pinfunction "8_8") (pintype "passive"))
      (node (ref "J25") (pin "9") (pinfunction "9_9") (pintype "passive"))
      (node (ref "J29") (pin "1") (pinfunction "1_1") (pintype "passive"))
      (node (ref "J29") (pin "10") (pinfunction "10_10") (pintype "passive"))
      (node (ref "J29") (pin "11") (pinfunction "11_11") (pintype "passive"))
      (node (ref "J29") (pin "12") (pinfunction "12_12") (pintype "passive"))
      (node (ref "J29") (pin "13") (pinfunction "13_13") (pintype "passive"))
      (node (ref "J29") (pin "14") (pinfunction "14_14") (pintype "passive"))
      (node (ref "J29") (pin "15") (pinfunction "15_15") (pintype "passive"))
      (node (ref "J29") (pin "2") (pinfunction "2_2") (pintype "passive"))
      (node (ref "J29") (pin "3") (pinfunction "3_3") (pintype "passive"))
      (node (ref "J29") (pin "4") (pinfunction "4_4") (pintype "passive"))
      (node (ref "J29") (pin "5") (pinfunction "5_5") (pintype "passive"))
      (node (ref "J29") (pin "6") (pinfunction "6_6") (pintype "passive"))
      (node (ref "J29") (pin "7") (pinfunction "7_7") (pintype "passive"))
      (node (ref "J29") (pin "8") (pinfunction "8_8") (pintype "passive"))
      (node (ref "J29") (pin "9") (pinfunction "9_9") (pintype "passive"))
    )
    (net (code "14") (name "Net-(J26-Pad1)") (class "Default")
      (node (ref "J26") (pin "1") (pinfunction "1_1") (pintype "passive"))
      (node (ref "J26") (pin "10") (pinfunction "10_10") (pintype "passive"))
      (node (ref "J26") (pin "11") (pinfunction "11_11") (pintype "passive"))
      (node (ref "J26") (pin "12") (pinfunction "12_12") (pintype "passive"))
      (node (ref "J26") (pin "13") (pinfunction "13_13") (pintype "passive"))
      (node (ref "J26") (pin "14") (pinfunction "14_14") (pintype "passive"))
      (node (ref "J26") (pin "15") (pinfunction "15_15") (pintype "passive"))
      (node (ref "J26") (pin "16") (pinfunction "16_16") (pintype "passive"))
      (node (ref "J26") (pin "17") (pinfunction "17_17") (pintype "passive"))
      (node (ref "J26") (pin "18") (pinfunction "18_18") (pintype "passive"))
      (node (ref "J26") (pin "19") (pinfunction "19_19") (pintype "passive"))
      (node (ref "J26") (pin "2") (pinfunction "2_2") (pintype "passive"))
      (node (ref "J26") (pin "3") (pinfunction "3_3") (pintype "passive"))
      (node (ref "J26") (pin "4") (pinfunction "4_4") (pintype "passive"))
      (node (ref "J26") (pin "5") (pinfunction "5_5") (pintype "passive"))
      (node (ref "J26") (pin "6") (pinfunction "6_6") (pintype "passive"))
      (node (ref "J26") (pin "7") (pinfunction "7_7") (pintype "passive"))
      (node (ref "J26") (pin "8") (pinfunction "8_8") (pintype "passive"))
      (node (ref "J26") (pin "9") (pinfunction "9_9") (pintype "passive"))
      (node (ref "J39") (pin "1") (pinfunction "1_1") (pintype "passive"))
      (node (ref "J39") (pin "10") (pinfunction "10_10") (pintype "passive"))
      (node (ref "J39") (pin "11") (pinfunction "11_11") (pintype "passive"))
      (node (ref "J39") (pin "12") (pinfunction "12_12") (pintype "passive"))
      (node (ref "J39") (pin "13") (pinfunction "13_13") (pintype "passive"))
      (node (ref "J39") (pin "14") (pinfunction "14_14") (pintype "passive"))
      (node (ref "J39") (pin "15") (pinfunction "15_15") (pintype "passive"))
      (node (ref "J39") (pin "16") (pinfunction "16_16") (pintype "passive"))
      (node (ref "J39") (pin "17") (pinfunction "17_17") (pintype "passive"))
      (node (ref "J39") (pin "18") (pinfunction "18_18") (pintype "passive"))
      (node (ref "J39") (pin "19") (pinfunction "19_19") (pintype "passive"))
      (node (ref "J39") (pin "2") (pinfunction "2_2") (pintype "passive"))
      (node (ref "J39") (pin "3") (pinfunction "3_3") (pintype "passive"))
      (node (ref "J39") (pin "4") (pinfunction "4_4") (pintype "passive"))
      (node (ref "J39") (pin "5") (pinfunction "5_5") (pintype "passive"))
      (node (ref "J39") (pin "6") (pinfunction "6_6") (pintype "passive"))
      (node (ref "J39") (pin "7") (pinfunction "7_7") (pintype "passive"))
      (node (ref "J39") (pin "8") (pinfunction "8_8") (pintype "passive"))
      (node (ref "J39") (pin "9") (pinfunction "9_9") (pintype "passive"))
    )
    (net (code "15") (name "Net-(J27-Pad1)") (class "Default")
      (node (ref "J27") (pin "1") (pinfunction "1_1") (pintype "passive"))
      (node (ref "J27") (pin "10") (pinfunction "10_10") (pintype "passive"))
      (node (ref "J27") (pin "11") (pinfunction "11_11") (pintype "passive"))
      (node (ref "J27") (pin "12") (pinfunction "12_12") (pintype "passive"))
      (node (ref "J27") (pin "13") (pinfunction "13_13") (pintype "passive"))
      (node (ref "J27") (pin "14") (pinfunction "14_14") (pintype "passive"))
      (node (ref "J27") (pin "15") (pinfunction "15_15") (pintype "passive"))
      (node (ref "J27") (pin "16") (pinfunction "16_16") (pintype "passive"))
      (node (ref "J27") (pin "17") (pinfunction "17_17") (pintype "passive"))
      (node (ref "J27") (pin "18") (pinfunction "18_18") (pintype "passive"))
      (node (ref "J27") (pin "19") (pinfunction "19_19") (pintype "passive"))
      (node (ref "J27") (pin "2") (pinfunction "2_2") (pintype "passive"))
      (node (ref "J27") (pin "3") (pinfunction "3_3") (pintype "passive"))
      (node (ref "J27") (pin "4") (pinfunction "4_4") (pintype "passive"))
      (node (ref "J27") (pin "5") (pinfunction "5_5") (pintype "passive"))
      (node (ref "J27") (pin "6") (pinfunction "6_6") (pintype "passive"))
      (node (ref "J27") (pin "7") (pinfunction "7_7") (pintype "passive"))
      (node (ref "J27") (pin "8") (pinfunction "8_8") (pintype "passive"))
      (node (ref "J27") (pin "9") (pinfunction "9_9") (pintype "passive"))
      (node (ref "J28") (pin "1") (pinfunction "1_1") (pintype "passive"))
      (node (ref "J28") (pin "10") (pinfunction "10_10") (pintype "passive"))
      (node (ref "J28") (pin "11") (pinfunction "11_11") (pintype "passive"))
      (node (ref "J28") (pin "12") (pinfunction "12_12") (pintype "passive"))
      (node (ref "J28") (pin "13") (pinfunction "13_13") (pintype "passive"))
      (node (ref "J28") (pin "14") (pinfunction "14_14") (pintype "passive"))
      (node (ref "J28") (pin "15") (pinfunction "15_15") (pintype "passive"))
      (node (ref "J28") (pin "16") (pinfunction "16_16") (pintype "passive"))
      (node (ref "J28") (pin "17") (pinfunction "17_17") (pintype "passive"))
      (node (ref "J28") (pin "18") (pinfunction "18_18") (pintype "passive"))
      (node (ref "J28") (pin "19") (pinfunction "19_19") (pintype "passive"))
      (node (ref "J28") (pin "2") (pinfunction "2_2") (pintype "passive"))
      (node (ref "J28") (pin "3") (pinfunction "3_3") (pintype "passive"))
      (node (ref "J28") (pin "4") (pinfunction "4_4") (pintype "passive"))
      (node (ref "J28") (pin "5") (pinfunction "5_5") (pintype "passive"))
      (node (ref "J28") (pin "6") (pinfunction "6_6") (pintype "passive"))
      (node (ref "J28") (pin "7") (pinfunction "7_7") (pintype "passive"))
      (node (ref "J28") (pin "8") (pinfunction "8_8") (pintype "passive"))
      (node (ref "J28") (pin "9") (pinfunction "9_9") (pintype "passive"))
    )
    (net (code "16") (name "Net-(J30-Pad1)") (class "Default")
      (node (ref "J30") (pin "1") (pinfunction "1_1") (pintype "passive"))
      (node (ref "J30") (pin "10") (pinfunction "10_10") (pintype "passive"))
      (node (ref "J30") (pin "11") (pinfunction "11_11") (pintype "passive"))
      (node (ref "J30") (pin "12") (pinfunction "12_12") (pintype "passive"))
      (node (ref "J30") (pin "13") (pinfunction "13_13") (pintype "passive"))
      (node (ref "J30") (pin "14") (pinfunction "14_14") (pintype "passive"))
      (node (ref "J30") (pin "15") (pinfunction "15_15") (pintype "passive"))
      (node (ref "J30") (pin "16") (pinfunction "16_16") (pintype "passive"))
      (node (ref "J30") (pin "17") (pinfunction "17_17") (pintype "passive"))
      (node (ref "J30") (pin "18") (pinfunction "18_18") (pintype "passive"))
      (node (ref "J30") (pin "19") (pinfunction "19_19") (pintype "passive"))
      (node (ref "J30") (pin "2") (pinfunction "2_2") (pintype "passive"))
      (node (ref "J30") (pin "3") (pinfunction "3_3") (pintype "passive"))
      (node (ref "J30") (pin "4") (pinfunction "4_4") (pintype "passive"))
      (node (ref "J30") (pin "5") (pinfunction "5_5") (pintype "passive"))
      (node (ref "J30") (pin "6") (pinfunction "6_6") (pintype "passive"))
      (node (ref "J30") (pin "7") (pinfunction "7_7") (pintype "passive"))
      (node (ref "J30") (pin "8") (pinfunction "8_8") (pintype "passive"))
      (node (ref "J30") (pin "9") (pinfunction "9_9") (pintype "passive"))
      (node (ref "J48") (pin "1") (pinfunction "1_1") (pintype "passive"))
      (node (ref "J48") (pin "10") (pinfunction "10_10") (pintype "passive"))
      (node (ref "J48") (pin "11") (pinfunction "11_11") (pintype "passive"))
      (node (ref "J48") (pin "12") (pinfunction "12_12") (pintype "passive"))
      (node (ref "J48") (pin "13") (pinfunction "13_13") (pintype "passive"))
      (node (ref "J48") (pin "14") (pinfunction "14_14") (pintype "passive"))
      (node (ref "J48") (pin "15") (pinfunction "15_15") (pintype "passive"))
      (node (ref "J48") (pin "16") (pinfunction "16_16") (pintype "passive"))
      (node (ref "J48") (pin "17") (pinfunction "17_17") (pintype "passive"))
      (node (ref "J48") (pin "18") (pinfunction "18_18") (pintype "passive"))
      (node (ref "J48") (pin "19") (pinfunction "19_19") (pintype "passive"))
      (node (ref "J48") (pin "2") (pinfunction "2_2") (pintype "passive"))
      (node (ref "J48") (pin "3") (pinfunction "3_3") (pintype "passive"))
      (node (ref "J48") (pin "4") (pinfunction "4_4") (pintype "passive"))
      (node (ref "J48") (pin "5") (pinfunction "5_5") (pintype "passive"))
      (node (ref "J48") (pin "6") (pinfunction "6_6") (pintype "passive"))
      (node (ref "J48") (pin "7") (pinfunction "7_7") (pintype "passive"))
      (node (ref "J48") (pin "8") (pinfunction "8_8") (pintype "passive"))
      (node (ref "J48") (pin "9") (pinfunction "9_9") (pintype "passive"))
    )
    (net (code "17") (name "Net-(J31-Pad1)") (class "Default")
      (node (ref "J31") (pin "1") (pinfunction "1_1") (pintype "passive"))
      (node (ref "J31") (pin "10") (pinfunction "10_10") (pintype "passive"))
      (node (ref "J31") (pin "11") (pinfunction "11_11") (pintype "passive"))
      (node (ref "J31") (pin "12") (pinfunction "12_12") (pintype "passive"))
      (node (ref "J31") (pin "13") (pinfunction "13_13") (pintype "passive"))
      (node (ref "J31") (pin "14") (pinfunction "14_14") (pintype "passive"))
      (node (ref "J31") (pin "15") (pinfunction "15_15") (pintype "passive"))
      (node (ref "J31") (pin "2") (pinfunction "2_2") (pintype "passive"))
      (node (ref "J31") (pin "3") (pinfunction "3_3") (pintype "passive"))
      (node (ref "J31") (pin "4") (pinfunction "4_4") (pintype "passive"))
      (node (ref "J31") (pin "5") (pinfunction "5_5") (pintype "passive"))
      (node (ref "J31") (pin "6") (pinfunction "6_6") (pintype "passive"))
      (node (ref "J31") (pin "7") (pinfunction "7_7") (pintype "passive"))
      (node (ref "J31") (pin "8") (pinfunction "8_8") (pintype "passive"))
      (node (ref "J31") (pin "9") (pinfunction "9_9") (pintype "passive"))
      (node (ref "J32") (pin "1") (pinfunction "1_1") (pintype "passive"))
      (node (ref "J32") (pin "10") (pinfunction "10_10") (pintype "passive"))
      (node (ref "J32") (pin "11") (pinfunction "11_11") (pintype "passive"))
      (node (ref "J32") (pin "12") (pinfunction "12_12") (pintype "passive"))
      (node (ref "J32") (pin "13") (pinfunction "13_13") (pintype "passive"))
      (node (ref "J32") (pin "14") (pinfunction "14_14") (pintype "passive"))
      (node (ref "J32") (pin "15") (pinfunction "15_15") (pintype "passive"))
      (node (ref "J32") (pin "2") (pinfunction "2_2") (pintype "passive"))
      (node (ref "J32") (pin "3") (pinfunction "3_3") (pintype "passive"))
      (node (ref "J32") (pin "4") (pinfunction "4_4") (pintype "passive"))
      (node (ref "J32") (pin "5") (pinfunction "5_5") (pintype "passive"))
      (node (ref "J32") (pin "6") (pinfunction "6_6") (pintype "passive"))
      (node (ref "J32") (pin "7") (pinfunction "7_7") (pintype "passive"))
      (node (ref "J32") (pin "8") (pinfunction "8_8") (pintype "passive"))
      (node (ref "J32") (pin "9") (pinfunction "9_9") (pintype "passive"))
    )
    (net (code "18") (name "Net-(J33-Pad1)") (class "Default")
      (node (ref "J33") (pin "1") (pinfunction "1_1") (pintype "passive"))
      (node (ref "J33") (pin "10") (pinfunction "10_10") (pintype "passive"))
      (node (ref "J33") (pin "11") (pinfunction "11_11") (pintype "passive"))
      (node (ref "J33") (pin "12") (pinfunction "12_12") (pintype "passive"))
      (node (ref "J33") (pin "13") (pinfunction "13_13") (pintype "passive"))
      (node (ref "J33") (pin "14") (pinfunction "14_14") (pintype "passive"))
      (node (ref "J33") (pin "15") (pinfunction "15_15") (pintype "passive"))
      (node (ref "J33") (pin "2") (pinfunction "2_2") (pintype "passive"))
      (node (ref "J33") (pin "3") (pinfunction "3_3") (pintype "passive"))
      (node (ref "J33") (pin "4") (pinfunction "4_4") (pintype "passive"))
      (node (ref "J33") (pin "5") (pinfunction "5_5") (pintype "passive"))
      (node (ref "J33") (pin "6") (pinfunction "6_6") (pintype "passive"))
      (node (ref "J33") (pin "7") (pinfunction "7_7") (pintype "passive"))
      (node (ref "J33") (pin "8") (pinfunction "8_8") (pintype "passive"))
      (node (ref "J33") (pin "9") (pinfunction "9_9") (pintype "passive"))
      (node (ref "J34") (pin "1") (pinfunction "1_1") (pintype "passive"))
      (node (ref "J34") (pin "10") (pinfunction "10_10") (pintype "passive"))
      (node (ref "J34") (pin "11") (pinfunction "11_11") (pintype "passive"))
      (node (ref "J34") (pin "12") (pinfunction "12_12") (pintype "passive"))
      (node (ref "J34") (pin "13") (pinfunction "13_13") (pintype "passive"))
      (node (ref "J34") (pin "14") (pinfunction "14_14") (pintype "passive"))
      (node (ref "J34") (pin "15") (pinfunction "15_15") (pintype "passive"))
      (node (ref "J34") (pin "2") (pinfunction "2_2") (pintype "passive"))
      (node (ref "J34") (pin "3") (pinfunction "3_3") (pintype "passive"))
      (node (ref "J34") (pin "4") (pinfunction "4_4") (pintype "passive"))
      (node (ref "J34") (pin "5") (pinfunction "5_5") (pintype "passive"))
      (node (ref "J34") (pin "6") (pinfunction "6_6") (pintype "passive"))
      (node (ref "J34") (pin "7") (pinfunction "7_7") (pintype "passive"))
      (node (ref "J34") (pin "8") (pinfunction "8_8") (pintype "passive"))
      (node (ref "J34") (pin "9") (pinfunction "9_9") (pintype "passive"))
    )
    (net (code "19") (name "Net-(J35-Pad1)") (class "Default")
      (node (ref "J35") (pin "1") (pinfunction "1_1") (pintype "passive"))
      (node (ref "J35") (pin "10") (pinfunction "10_10") (pintype "passive"))
      (node (ref "J35") (pin "11") (pinfunction "11_11") (pintype "passive"))
      (node (ref "J35") (pin "12") (pinfunction "12_12") (pintype "passive"))
      (node (ref "J35") (pin "13") (pinfunction "13_13") (pintype "passive"))
      (node (ref "J35") (pin "14") (pinfunction "14_14") (pintype "passive"))
      (node (ref "J35") (pin "15") (pinfunction "15_15") (pintype "passive"))
      (node (ref "J35") (pin "2") (pinfunction "2_2") (pintype "passive"))
      (node (ref "J35") (pin "3") (pinfunction "3_3") (pintype "passive"))
      (node (ref "J35") (pin "4") (pinfunction "4_4") (pintype "passive"))
      (node (ref "J35") (pin "5") (pinfunction "5_5") (pintype "passive"))
      (node (ref "J35") (pin "6") (pinfunction "6_6") (pintype "passive"))
      (node (ref "J35") (pin "7") (pinfunction "7_7") (pintype "passive"))
      (node (ref "J35") (pin "8") (pinfunction "8_8") (pintype "passive"))
      (node (ref "J35") (pin "9") (pinfunction "9_9") (pintype "passive"))
      (node (ref "J36") (pin "1") (pinfunction "1_1") (pintype "passive"))
      (node (ref "J36") (pin "10") (pinfunction "10_10") (pintype "passive"))
      (node (ref "J36") (pin "11") (pinfunction "11_11") (pintype "passive"))
      (node (ref "J36") (pin "12") (pinfunction "12_12") (pintype "passive"))
      (node (ref "J36") (pin "13") (pinfunction "13_13") (pintype "passive"))
      (node (ref "J36") (pin "14") (pinfunction "14_14") (pintype "passive"))
      (node (ref "J36") (pin "15") (pinfunction "15_15") (pintype "passive"))
      (node (ref "J36") (pin "2") (pinfunction "2_2") (pintype "passive"))
      (node (ref "J36") (pin "3") (pinfunction "3_3") (pintype "passive"))
      (node (ref "J36") (pin "4") (pinfunction "4_4") (pintype "passive"))
      (node (ref "J36") (pin "5") (pinfunction "5_5") (pintype "passive"))
      (node (ref "J36") (pin "6") (pinfunction "6_6") (pintype "passive"))
      (node (ref "J36") (pin "7") (pinfunction "7_7") (pintype "passive"))
      (node (ref "J36") (pin "8") (pinfunction "8_8") (pintype "passive"))
      (node (ref "J36") (pin "9") (pinfunction "9_9") (pintype "passive"))
    )
    (net (code "20") (name "Net-(J37-Pad1)") (class "Default")
      (node (ref "J37") (pin "1") (pinfunction "1_1") (pintype "passive"))
      (node (ref "J37") (pin "10") (pinfunction "10_10") (pintype "passive"))
      (node (ref "J37") (pin "11") (pinfunction "11_11") (pintype "passive"))
      (node (ref "J37") (pin "12") (pinfunction "12_12") (pintype "passive"))
      (node (ref "J37") (pin "13") (pinfunction "13_13") (pintype "passive"))
      (node (ref "J37") (pin "14") (pinfunction "14_14") (pintype "passive"))
      (node (ref "J37") (pin "15") (pinfunction "15_15") (pintype "passive"))
      (node (ref "J37") (pin "2") (pinfunction "2_2") (pintype "passive"))
      (node (ref "J37") (pin "3") (pinfunction "3_3") (pintype "passive"))
      (node (ref "J37") (pin "4") (pinfunction "4_4") (pintype "passive"))
      (node (ref "J37") (pin "5") (pinfunction "5_5") (pintype "passive"))
      (node (ref "J37") (pin "6") (pinfunction "6_6") (pintype "passive"))
      (node (ref "J37") (pin "7") (pinfunction "7_7") (pintype "passive"))
      (node (ref "J37") (pin "8") (pinfunction "8_8") (pintype "passive"))
      (node (ref "J37") (pin "9") (pinfunction "9_9") (pintype "passive"))
      (node (ref "J38") (pin "1") (pinfunction "1_1") (pintype "passive"))
      (node (ref "J38") (pin "10") (pinfunction "10_10") (pintype "passive"))
      (node (ref "J38") (pin "11") (pinfunction "11_11") (pintype "passive"))
      (node (ref "J38") (pin "12") (pinfunction "12_12") (pintype "passive"))
      (node (ref "J38") (pin "13") (pinfunction "13_13") (pintype "passive"))
      (node (ref "J38") (pin "14") (pinfunction "14_14") (pintype "passive"))
      (node (ref "J38") (pin "15") (pinfunction "15_15") (pintype "passive"))
      (node (ref "J38") (pin "2") (pinfunction "2_2") (pintype "passive"))
      (node (ref "J38") (pin "3") (pinfunction "3_3") (pintype "passive"))
      (node (ref "J38") (pin "4") (pinfunction "4_4") (pintype "passive"))
      (node (ref "J38") (pin "5") (pinfunction "5_5") (pintype "passive"))
      (node (ref "J38") (pin "6") (pinfunction "6_6") (pintype "passive"))
      (node (ref "J38") (pin "7") (pinfunction "7_7") (pintype "passive"))
      (node (ref "J38") (pin "8") (pinfunction "8_8") (pintype "passive"))
      (node (ref "J38") (pin "9") (pinfunction "9_9") (pintype "passive"))
    )
    (net (code "21") (name "Net-(J40-Pad1)") (class "Default")
      (node (ref "J40") (pin "1") (pinfunction "1_1") (pintype "passive"))
      (node (ref "J40") (pin "10") (pinfunction "10_10") (pintype "passive"))
      (node (ref "J40") (pin "11") (pinfunction "11_11") (pintype "passive"))
      (node (ref "J40") (pin "12") (pinfunction "12_12") (pintype "passive"))
      (node (ref "J40") (pin "13") (pinfunction "13_13") (pintype "passive"))
      (node (ref "J40") (pin "14") (pinfunction "14_14") (pintype "passive"))
      (node (ref "J40") (pin "15") (pinfunction "15_15") (pintype "passive"))
      (node (ref "J40") (pin "16") (pinfunction "16_16") (pintype "passive"))
      (node (ref "J40") (pin "17") (pinfunction "17_17") (pintype "passive"))
      (node (ref "J40") (pin "18") (pinfunction "18_18") (pintype "passive"))
      (node (ref "J40") (pin "19") (pinfunction "19_19") (pintype "passive"))
      (node (ref "J40") (pin "2") (pinfunction "2_2") (pintype "passive"))
      (node (ref "J40") (pin "3") (pinfunction "3_3") (pintype "passive"))
      (node (ref "J40") (pin "4") (pinfunction "4_4") (pintype "passive"))
      (node (ref "J40") (pin "5") (pinfunction "5_5") (pintype "passive"))
      (node (ref "J40") (pin "6") (pinfunction "6_6") (pintype "passive"))
      (node (ref "J40") (pin "7") (pinfunction "7_7") (pintype "passive"))
      (node (ref "J40") (pin "8") (pinfunction "8_8") (pintype "passive"))
      (node (ref "J40") (pin "9") (pinfunction "9_9") (pintype "passive"))
      (node (ref "J41") (pin "1") (pinfunction "1_1") (pintype "passive"))
      (node (ref "J41") (pin "10") (pinfunction "10_10") (pintype "passive"))
      (node (ref "J41") (pin "11") (pinfunction "11_11") (pintype "passive"))
      (node (ref "J41") (pin "12") (pinfunction "12_12") (pintype "passive"))
      (node (ref "J41") (pin "13") (pinfunction "13_13") (pintype "passive"))
      (node (ref "J41") (pin "14") (pinfunction "14_14") (pintype "passive"))
      (node (ref "J41") (pin "15") (pinfunction "15_15") (pintype "passive"))
      (node (ref "J41") (pin "16") (pinfunction "16_16") (pintype "passive"))
      (node (ref "J41") (pin "17") (pinfunction "17_17") (pintype "passive"))
      (node (ref "J41") (pin "18") (pinfunction "18_18") (pintype "passive"))
      (node (ref "J41") (pin "19") (pinfunction "19_19") (pintype "passive"))
      (node (ref "J41") (pin "2") (pinfunction "2_2") (pintype "passive"))
      (node (ref "J41") (pin "3") (pinfunction "3_3") (pintype "passive"))
      (node (ref "J41") (pin "4") (pinfunction "4_4") (pintype "passive"))
      (node (ref "J41") (pin "5") (pinfunction "5_5") (pintype "passive"))
      (node (ref "J41") (pin "6") (pinfunction "6_6") (pintype "passive"))
      (node (ref "J41") (pin "7") (pinfunction "7_7") (pintype "passive"))
      (node (ref "J41") (pin "8") (pinfunction "8_8") (pintype "passive"))
      (node (ref "J41") (pin "9") (pinfunction "9_9") (pintype "passive"))
    )
    (net (code "22") (name "Net-(J42-Pad1)") (class "Default")
      (node (ref "J42") (pin "1") (pinfunction "1_1") (pintype "passive"))
      (node (ref "J42") (pin "10") (pinfunction "10_10") (pintype "passive"))
      (node (ref "J42") (pin "11") (pinfunction "11_11") (pintype "passive"))
      (node (ref "J42") (pin "12") (pinfunction "12_12") (pintype "passive"))
      (node (ref "J42") (pin "13") (pinfunction "13_13") (pintype "passive"))
      (node (ref "J42") (pin "14") (pinfunction "14_14") (pintype "passive"))
      (node (ref "J42") (pin "15") (pinfunction "15_15") (pintype "passive"))
      (node (ref "J42") (pin "16") (pinfunction "16_16") (pintype "passive"))
      (node (ref "J42") (pin "17") (pinfunction "17_17") (pintype "passive"))
      (node (ref "J42") (pin "18") (pinfunction "18_18") (pintype "passive"))
      (node (ref "J42") (pin "19") (pinfunction "19_19") (pintype "passive"))
      (node (ref "J42") (pin "2") (pinfunction "2_2") (pintype "passive"))
      (node (ref "J42") (pin "3") (pinfunction "3_3") (pintype "passive"))
      (node (ref "J42") (pin "4") (pinfunction "4_4") (pintype "passive"))
      (node (ref "J42") (pin "5") (pinfunction "5_5") (pintype "passive"))
      (node (ref "J42") (pin "6") (pinfunction "6_6") (pintype "passive"))
      (node (ref "J42") (pin "7") (pinfunction "7_7") (pintype "passive"))
      (node (ref "J42") (pin "8") (pinfunction "8_8") (pintype "passive"))
      (node (ref "J42") (pin "9") (pinfunction "9_9") (pintype "passive"))
      (node (ref "J43") (pin "1") (pinfunction "1_1") (pintype "passive"))
      (node (ref "J43") (pin "10") (pinfunction "10_10") (pintype "passive"))
      (node (ref "J43") (pin "11") (pinfunction "11_11") (pintype "passive"))
      (node (ref "J43") (pin "12") (pinfunction "12_12") (pintype "passive"))
      (node (ref "J43") (pin "13") (pinfunction "13_13") (pintype "passive"))
      (node (ref "J43") (pin "14") (pinfunction "14_14") (pintype "passive"))
      (node (ref "J43") (pin "15") (pinfunction "15_15") (pintype "passive"))
      (node (ref "J43") (pin "16") (pinfunction "16_16") (pintype "passive"))
      (node (ref "J43") (pin "17") (pinfunction "17_17") (pintype "passive"))
      (node (ref "J43") (pin "18") (pinfunction "18_18") (pintype "passive"))
      (node (ref "J43") (pin "19") (pinfunction "19_19") (pintype "passive"))
      (node (ref "J43") (pin "2") (pinfunction "2_2") (pintype "passive"))
      (node (ref "J43") (pin "3") (pinfunction "3_3") (pintype "passive"))
      (node (ref "J43") (pin "4") (pinfunction "4_4") (pintype "passive"))
      (node (ref "J43") (pin "5") (pinfunction "5_5") (pintype "passive"))
      (node (ref "J43") (pin "6") (pinfunction "6_6") (pintype "passive"))
      (node (ref "J43") (pin "7") (pinfunction "7_7") (pintype "passive"))
      (node (ref "J43") (pin "8") (pinfunction "8_8") (pintype "passive"))
      (node (ref "J43") (pin "9") (pinfunction "9_9") (pintype "passive"))
    )
    (net (code "23") (name "Net-(J44-Pad1)") (class "Default")
      (node (ref "J44") (pin "1") (pinfunction "1_1") (pintype "passive"))
      (node (ref "J44") (pin "10") (pinfunction "10_10") (pintype "passive"))
      (node (ref "J44") (pin "11") (pinfunction "11_11") (pintype "passive"))
      (node (ref "J44") (pin "12") (pinfunction "12_12") (pintype "passive"))
      (node (ref "J44") (pin "13") (pinfunction "13_13") (pintype "passive"))
      (node (ref "J44") (pin "14") (pinfunction "14_14") (pintype "passive"))
      (node (ref "J44") (pin "15") (pinfunction "15_15") (pintype "passive"))
      (node (ref "J44") (pin "16") (pinfunction "16_16") (pintype "passive"))
      (node (ref "J44") (pin "17") (pinfunction "17_17") (pintype "passive"))
      (node (ref "J44") (pin "18") (pinfunction "18_18") (pintype "passive"))
      (node (ref "J44") (pin "19") (pinfunction "19_19") (pintype "passive"))
      (node (ref "J44") (pin "2") (pinfunction "2_2") (pintype "passive"))
      (node (ref "J44") (pin "3") (pinfunction "3_3") (pintype "passive"))
      (node (ref "J44") (pin "4") (pinfunction "4_4") (pintype "passive"))
      (node (ref "J44") (pin "5") (pinfunction "5_5") (pintype "passive"))
      (node (ref "J44") (pin "6") (pinfunction "6_6") (pintype "passive"))
      (node (ref "J44") (pin "7") (pinfunction "7_7") (pintype "passive"))
      (node (ref "J44") (pin "8") (pinfunction "8_8") (pintype "passive"))
      (node (ref "J44") (pin "9") (pinfunction "9_9") (pintype "passive"))
      (node (ref "J45") (pin "1") (pinfunction "1_1") (pintype "passive"))
      (node (ref "J45") (pin "10") (pinfunction "10_10") (pintype "passive"))
      (node (ref "J45") (pin "11") (pinfunction "11_11") (pintype "passive"))
      (node (ref "J45") (pin "12") (pinfunction "12_12") (pintype "passive"))
      (node (ref "J45") (pin "13") (pinfunction "13_13") (pintype "passive"))
      (node (ref "J45") (pin "14") (pinfunction "14_14") (pintype "passive"))
      (node (ref "J45") (pin "15") (pinfunction "15_15") (pintype "passive"))
      (node (ref "J45") (pin "16") (pinfunction "16_16") (pintype "passive"))
      (node (ref "J45") (pin "17") (pinfunction "17_17") (pintype "passive"))
      (node (ref "J45") (pin "18") (pinfunction "18_18") (pintype "passive"))
      (node (ref "J45") (pin "19") (pinfunction "19_19") (pintype "passive"))
      (node (ref "J45") (pin "2") (pinfunction "2_2") (pintype "passive"))
      (node (ref "J45") (pin "3") (pinfunction "3_3") (pintype "passive"))
      (node (ref "J45") (pin "4") (pinfunction "4_4") (pintype "passive"))
      (node (ref "J45") (pin "5") (pinfunction "5_5") (pintype "passive"))
      (node (ref "J45") (pin "6") (pinfunction "6_6") (pintype "passive"))
      (node (ref "J45") (pin "7") (pinfunction "7_7") (pintype "passive"))
      (node (ref "J45") (pin "8") (pinfunction "8_8") (pintype "passive"))
      (node (ref "J45") (pin "9") (pinfunction "9_9") (pintype "passive"))
    )
    (net (code "24") (name "Net-(J46-Pad1)") (class "Default")
      (node (ref "J46") (pin "1") (pinfunction "1_1") (pintype "passive"))
      (node (ref "J46") (pin "10") (pinfunction "10_10") (pintype "passive"))
      (node (ref "J46") (pin "11") (pinfunction "11_11") (pintype "passive"))
      (node (ref "J46") (pin "12") (pinfunction "12_12") (pintype "passive"))
      (node (ref "J46") (pin "13") (pinfunction "13_13") (pintype "passive"))
      (node (ref "J46") (pin "14") (pinfunction "14_14") (pintype "passive"))
      (node (ref "J46") (pin "15") (pinfunction "15_15") (pintype "passive"))
      (node (ref "J46") (pin "16") (pinfunction "16_16") (pintype "passive"))
      (node (ref "J46") (pin "17") (pinfunction "17_17") (pintype "passive"))
      (node (ref "J46") (pin "18") (pinfunction "18_18") (pintype "passive"))
      (node (ref "J46") (pin "19") (pinfunction "19_19") (pintype "passive"))
      (node (ref "J46") (pin "2") (pinfunction "2_2") (pintype "passive"))
      (node (ref "J46") (pin "3") (pinfunction "3_3") (pintype "passive"))
      (node (ref "J46") (pin "4") (pinfunction "4_4") (pintype "passive"))
      (node (ref "J46") (pin "5") (pinfunction "5_5") (pintype "passive"))
      (node (ref "J46") (pin "6") (pinfunction "6_6") (pintype "passive"))
      (node (ref "J46") (pin "7") (pinfunction "7_7") (pintype "passive"))
      (node (ref "J46") (pin "8") (pinfunction "8_8") (pintype "passive"))
      (node (ref "J46") (pin "9") (pinfunction "9_9") (pintype "passive"))
      (node (ref "J47") (pin "1") (pinfunction "1_1") (pintype "passive"))
      (node (ref "J47") (pin "10") (pinfunction "10_10") (pintype "passive"))
      (node (ref "J47") (pin "11") (pinfunction "11_11") (pintype "passive"))
      (node (ref "J47") (pin "12") (pinfunction "12_12") (pintype "passive"))
      (node (ref "J47") (pin "13") (pinfunction "13_13") (pintype "passive"))
      (node (ref "J47") (pin "14") (pinfunction "14_14") (pintype "passive"))
      (node (ref "J47") (pin "15") (pinfunction "15_15") (pintype "passive"))
      (node (ref "J47") (pin "16") (pinfunction "16_16") (pintype "passive"))
      (node (ref "J47") (pin "17") (pinfunction "17_17") (pintype "passive"))
      (node (ref "J47") (pin "18") (pinfunction "18_18") (pintype "passive"))
      (node (ref "J47") (pin "19") (pinfunction "19_19") (pintype "passive"))
      (node (ref "J47") (pin "2") (pinfunction "2_2") (pintype "passive"))
      (node (ref "J47") (pin "3") (pinfunction "3_3") (pintype "passive"))
      (node (ref "J47") (pin "4") (pinfunction "4_4") (pintype "passive"))
      (node (ref "J47") (pin "5") (pinfunction "5_5") (pintype "passive"))
      (node (ref "J47") (pin "6") (pinfunction "6_6") (pintype "passive"))
      (node (ref "J47") (pin "7") (pinfunction "7_7") (pintype "passive"))
      (node (ref "J47") (pin "8") (pinfunction "8_8") (pintype "passive"))
      (node (ref "J47") (pin "9") (pinfunction "9_9") (pintype "passive"))
    )
    (net (code "25") (name "Net-(J49-Pad1)") (class "Default")
      (node (ref "J49") (pin "1") (pinfunction "1_1") (pintype "passive"))
      (node (ref "J49") (pin "10") (pinfunction "10_10") (pintype "passive"))
      (node (ref "J49") (pin "11") (pinfunction "11_11") (pintype "passive"))
      (node (ref "J49") (pin "12") (pinfunction "12_12") (pintype "passive"))
      (node (ref "J49") (pin "13") (pinfunction "13_13") (pintype "passive"))
      (node (ref "J49") (pin "14") (pinfunction "14_14") (pintype "passive"))
      (node (ref "J49") (pin "15") (pinfunction "15_15") (pintype "passive"))
      (node (ref "J49") (pin "16") (pinfunction "16_16") (pintype "passive"))
      (node (ref "J49") (pin "17") (pinfunction "17_17") (pintype "passive"))
      (node (ref "J49") (pin "18") (pinfunction "18_18") (pintype "passive"))
      (node (ref "J49") (pin "19") (pinfunction "19_19") (pintype "passive"))
      (node (ref "J49") (pin "2") (pinfunction "2_2") (pintype "passive"))
      (node (ref "J49") (pin "3") (pinfunction "3_3") (pintype "passive"))
      (node (ref "J49") (pin "4") (pinfunction "4_4") (pintype "passive"))
      (node (ref "J49") (pin "5") (pinfunction "5_5") (pintype "passive"))
      (node (ref "J49") (pin "6") (pinfunction "6_6") (pintype "passive"))
      (node (ref "J49") (pin "7") (pinfunction "7_7") (pintype "passive"))
      (node (ref "J49") (pin "8") (pinfunction "8_8") (pintype "passive"))
      (node (ref "J49") (pin "9") (pinfunction "9_9") (pintype "passive"))
      (node (ref "J50") (pin "1") (pinfunction "1_1") (pintype "passive"))
      (node (ref "J50") (pin "10") (pinfunction "10_10") (pintype "passive"))
      (node (ref "J50") (pin "11") (pinfunction "11_11") (pintype "passive"))
      (node (ref "J50") (pin "12") (pinfunction "12_12") (pintype "passive"))
      (node (ref "J50") (pin "13") (pinfunction "13_13") (pintype "passive"))
      (node (ref "J50") (pin "14") (pinfunction "14_14") (pintype "passive"))
      (node (ref "J50") (pin "15") (pinfunction "15_15") (pintype "passive"))
      (node (ref "J50") (pin "16") (pinfunction "16_16") (pintype "passive"))
      (node (ref "J50") (pin "17") (pinfunction "17_17") (pintype "passive"))
      (node (ref "J50") (pin "18") (pinfunction "18_18") (pintype "passive"))
      (node (ref "J50") (pin "19") (pinfunction "19_19") (pintype "passive"))
      (node (ref "J50") (pin "2") (pinfunction "2_2") (pintype "passive"))
      (node (ref "J50") (pin "3") (pinfunction "3_3") (pintype "passive"))
      (node (ref "J50") (pin "4") (pinfunction "4_4") (pintype "passive"))
      (node (ref "J50") (pin "5") (pinfunction "5_5") (pintype "passive"))
      (node (ref "J50") (pin "6") (pinfunction "6_6") (pintype "passive"))
      (node (ref "J50") (pin "7") (pinfunction "7_7") (pintype "passive"))
      (node (ref "J50") (pin "8") (pinfunction "8_8") (pintype "passive"))
      (node (ref "J50") (pin "9") (pinfunction "9_9") (pintype "passive"))
    )
    (net (code "26") (name "Net-(J51-Pad1)") (class "Default")
      (node (ref "J51") (pin "1") (pinfunction "1_1") (pintype "passive"))
      (node (ref "J51") (pin "10") (pinfunction "10_10") (pintype "passive"))
      (node (ref "J51") (pin "11") (pinfunction "11_11") (pintype "passive"))
      (node (ref "J51") (pin "12") (pinfunction "12_12") (pintype "passive"))
      (node (ref "J51") (pin "13") (pinfunction "13_13") (pintype "passive"))
      (node (ref "J51") (pin "14") (pinfunction "14_14") (pintype "passive"))
      (node (ref "J51") (pin "15") (pinfunction "15_15") (pintype "passive"))
      (node (ref "J51") (pin "16") (pinfunction "16_16") (pintype "passive"))
      (node (ref "J51") (pin "17") (pinfunction "17_17") (pintype "passive"))
      (node (ref "J51") (pin "18") (pinfunction "18_18") (pintype "passive"))
      (node (ref "J51") (pin "19") (pinfunction "19_19") (pintype "passive"))
      (node (ref "J51") (pin "2") (pinfunction "2_2") (pintype "passive"))
      (node (ref "J51") (pin "3") (pinfunction "3_3") (pintype "passive"))
      (node (ref "J51") (pin "4") (pinfunction "4_4") (pintype "passive"))
      (node (ref "J51") (pin "5") (pinfunction "5_5") (pintype "passive"))
      (node (ref "J51") (pin "6") (pinfunction "6_6") (pintype "passive"))
      (node (ref "J51") (pin "7") (pinfunction "7_7") (pintype "passive"))
      (node (ref "J51") (pin "8") (pinfunction "8_8") (pintype "passive"))
      (node (ref "J51") (pin "9") (pinfunction "9_9") (pintype "passive"))
      (node (ref "J52") (pin "1") (pinfunction "1_1") (pintype "passive"))
      (node (ref "J52") (pin "10") (pinfunction "10_10") (pintype "passive"))
      (node (ref "J52") (pin "11") (pinfunction "11_11") (pintype "passive"))
      (node (ref "J52") (pin "12") (pinfunction "12_12") (pintype "passive"))
      (node (ref "J52") (pin "13") (pinfunction "13_13") (pintype "passive"))
      (node (ref "J52") (pin "14") (pinfunction "14_14") (pintype "passive"))
      (node (ref "J52") (pin "15") (pinfunction "15_15") (pintype "passive"))
      (node (ref "J52") (pin "16") (pinfunction "16_16") (pintype "passive"))
      (node (ref "J52") (pin "17") (pinfunction "17_17") (pintype "passive"))
      (node (ref "J52") (pin "18") (pinfunction "18_18") (pintype "passive"))
      (node (ref "J52") (pin "19") (pinfunction "19_19") (pintype "passive"))
      (node (ref "J52") (pin "2") (pinfunction "2_2") (pintype "passive"))
      (node (ref "J52") (pin "3") (pinfunction "3_3") (pintype "passive"))
      (node (ref "J52") (pin "4") (pinfunction "4_4") (pintype "passive"))
      (node (ref "J52") (pin "5") (pinfunction "5_5") (pintype "passive"))
      (node (ref "J52") (pin "6") (pinfunction "6_6") (pintype "passive"))
      (node (ref "J52") (pin "7") (pinfunction "7_7") (pintype "passive"))
      (node (ref "J52") (pin "8") (pinfunction "8_8") (pintype "passive"))
      (node (ref "J52") (pin "9") (pinfunction "9_9") (pintype "passive"))
    )
    (net (code "27") (name "Net-(J53-Pad1)") (class "Default")
      (node (ref "J53") (pin "1") (pinfunction "1_1") (pintype "passive"))
      (node (ref "J53") (pin "10") (pinfunction "10_10") (pintype "passive"))
      (node (ref "J53") (pin "11") (pinfunction "11_11") (pintype "passive"))
      (node (ref "J53") (pin "12") (pinfunction "12_12") (pintype "passive"))
      (node (ref "J53") (pin "13") (pinfunction "13_13") (pintype "passive"))
      (node (ref "J53") (pin "14") (pinfunction "14_14") (pintype "passive"))
      (node (ref "J53") (pin "15") (pinfunction "15_15") (pintype "passive"))
      (node (ref "J53") (pin "16") (pinfunction "16_16") (pintype "passive"))
      (node (ref "J53") (pin "17") (pinfunction "17_17") (pintype "passive"))
      (node (ref "J53") (pin "18") (pinfunction "18_18") (pintype "passive"))
      (node (ref "J53") (pin "19") (pinfunction "19_19") (pintype "passive"))
      (node (ref "J53") (pin "2") (pinfunction "2_2") (pintype "passive"))
      (node (ref "J53") (pin "3") (pinfunction "3_3") (pintype "passive"))
      (node (ref "J53") (pin "4") (pinfunction "4_4") (pintype "passive"))
      (node (ref "J53") (pin "5") (pinfunction "5_5") (pintype "passive"))
      (node (ref "J53") (pin "6") (pinfunction "6_6") (pintype "passive"))
      (node (ref "J53") (pin "7") (pinfunction "7_7") (pintype "passive"))
      (node (ref "J53") (pin "8") (pinfunction "8_8") (pintype "passive"))
      (node (ref "J53") (pin "9") (pinfunction "9_9") (pintype "passive"))
      (node (ref "J54") (pin "1") (pinfunction "1_1") (pintype "passive"))
      (node (ref "J54") (pin "10") (pinfunction "10_10") (pintype "passive"))
      (node (ref "J54") (pin "11") (pinfunction "11_11") (pintype "passive"))
      (node (ref "J54") (pin "12") (pinfunction "12_12") (pintype "passive"))
      (node (ref "J54") (pin "13") (pinfunction "13_13") (pintype "passive"))
      (node (ref "J54") (pin "14") (pinfunction "14_14") (pintype "passive"))
      (node (ref "J54") (pin "15") (pinfunction "15_15") (pintype "passive"))
      (node (ref "J54") (pin "16") (pinfunction "16_16") (pintype "passive"))
      (node (ref "J54") (pin "17") (pinfunction "17_17") (pintype "passive"))
      (node (ref "J54") (pin "18") (pinfunction "18_18") (pintype "passive"))
      (node (ref "J54") (pin "19") (pinfunction "19_19") (pintype "passive"))
      (node (ref "J54") (pin "2") (pinfunction "2_2") (pintype "passive"))
      (node (ref "J54") (pin "3") (pinfunction "3_3") (pintype "passive"))
      (node (ref "J54") (pin "4") (pinfunction "4_4") (pintype "passive"))
      (node (ref "J54") (pin "5") (pinfunction "5_5") (pintype "passive"))
      (node (ref "J54") (pin "6") (pinfunction "6_6") (pintype "passive"))
      (node (ref "J54") (pin "7") (pinfunction "7_7") (pintype "passive"))
      (node (ref "J54") (pin "8") (pinfunction "8_8") (pintype "passive"))
      (node (ref "J54") (pin "9") (pinfunction "9_9") (pintype "passive"))
    )
    (net (code "28") (name "Net-(J55-Pad1)") (class "Default")
      (node (ref "J55") (pin "1") (pinfunction "1_1") (pintype "passive"))
      (node (ref "J55") (pin "10") (pinfunction "10_10") (pintype "passive"))
      (node (ref "J55") (pin "11") (pinfunction "11_11") (pintype "passive"))
      (node (ref "J55") (pin "12") (pinfunction "12_12") (pintype "passive"))
      (node (ref "J55") (pin "13") (pinfunction "13_13") (pintype "passive"))
      (node (ref "J55") (pin "14") (pinfunction "14_14") (pintype "passive"))
      (node (ref "J55") (pin "15") (pinfunction "15_15") (pintype "passive"))
      (node (ref "J55") (pin "16") (pinfunction "16_16") (pintype "passive"))
      (node (ref "J55") (pin "17") (pinfunction "17_17") (pintype "passive"))
      (node (ref "J55") (pin "18") (pinfunction "18_18") (pintype "passive"))
      (node (ref "J55") (pin "19") (pinfunction "19_19") (pintype "passive"))
      (node (ref "J55") (pin "2") (pinfunction "2_2") (pintype "passive"))
      (node (ref "J55") (pin "3") (pinfunction "3_3") (pintype "passive"))
      (node (ref "J55") (pin "4") (pinfunction "4_4") (pintype "passive"))
      (node (ref "J55") (pin "5") (pinfunction "5_5") (pintype "passive"))
      (node (ref "J55") (pin "6") (pinfunction "6_6") (pintype "passive"))
      (node (ref "J55") (pin "7") (pinfunction "7_7") (pintype "passive"))
      (node (ref "J55") (pin "8") (pinfunction "8_8") (pintype "passive"))
      (node (ref "J55") (pin "9") (pinfunction "9_9") (pintype "passive"))
      (node (ref "J56") (pin "1") (pinfunction "1_1") (pintype "passive"))
      (node (ref "J56") (pin "10") (pinfunction "10_10") (pintype "passive"))
      (node (ref "J56") (pin "11") (pinfunction "11_11") (pintype "passive"))
      (node (ref "J56") (pin "12") (pinfunction "12_12") (pintype "passive"))
      (node (ref "J56") (pin "13") (pinfunction "13_13") (pintype "passive"))
      (node (ref "J56") (pin "14") (pinfunction "14_14") (pintype "passive"))
      (node (ref "J56") (pin "15") (pinfunction "15_15") (pintype "passive"))
      (node (ref "J56") (pin "16") (pinfunction "16_16") (pintype "passive"))
      (node (ref "J56") (pin "17") (pinfunction "17_17") (pintype "passive"))
      (node (ref "J56") (pin "18") (pinfunction "18_18") (pintype "passive"))
      (node (ref "J56") (pin "19") (pinfunction "19_19") (pintype "passive"))
      (node (ref "J56") (pin "2") (pinfunction "2_2") (pintype "passive"))
      (node (ref "J56") (pin "3") (pinfunction "3_3") (pintype "passive"))
      (node (ref "J56") (pin "4") (pinfunction "4_4") (pintype "passive"))
      (node (ref "J56") (pin "5") (pinfunction "5_5") (pintype "passive"))
      (node (ref "J56") (pin "6") (pinfunction "6_6") (pintype "passive"))
      (node (ref "J56") (pin "7") (pinfunction "7_7") (pintype "passive"))
      (node (ref "J56") (pin "8") (pinfunction "8_8") (pintype "passive"))
      (node (ref "J56") (pin "9") (pinfunction "9_9") (pintype "passive"))
    )
    (net (code "29") (name "Net-(J57-Pad1)") (class "Default")
      (node (ref "J57") (pin "1") (pinfunction "1_1") (pintype "passive"))
      (node (ref "J57") (pin "10") (pinfunction "10_10") (pintype "passive"))
      (node (ref "J57") (pin "11") (pinfunction "11_11") (pintype "passive"))
      (node (ref "J57") (pin "12") (pinfunction "12_12") (pintype "passive"))
      (node (ref "J57") (pin "13") (pinfunction "13_13") (pintype "passive"))
      (node (ref "J57") (pin "14") (pinfunction "14_14") (pintype "passive"))
      (node (ref "J57") (pin "15") (pinfunction "15_15") (pintype "passive"))
      (node (ref "J57") (pin "16") (pinfunction "16_16") (pintype "passive"))
      (node (ref "J57") (pin "17") (pinfunction "17_17") (pintype "passive"))
      (node (ref "J57") (pin "18") (pinfunction "18_18") (pintype "passive"))
      (node (ref "J57") (pin "19") (pinfunction "19_19") (pintype "passive"))
      (node (ref "J57") (pin "2") (pinfunction "2_2") (pintype "passive"))
      (node (ref "J57") (pin "3") (pinfunction "3_3") (pintype "passive"))
      (node (ref "J57") (pin "4") (pinfunction "4_4") (pintype "passive"))
      (node (ref "J57") (pin "5") (pinfunction "5_5") (pintype "passive"))
      (node (ref "J57") (pin "6") (pinfunction "6_6") (pintype "passive"))
      (node (ref "J57") (pin "7") (pinfunction "7_7") (pintype "passive"))
      (node (ref "J57") (pin "8") (pinfunction "8_8") (pintype "passive"))
      (node (ref "J57") (pin "9") (pinfunction "9_9") (pintype "passive"))
      (node (ref "J58") (pin "1") (pinfunction "1_1") (pintype "passive"))
      (node (ref "J58") (pin "10") (pinfunction "10_10") (pintype "passive"))
      (node (ref "J58") (pin "11") (pinfunction "11_11") (pintype "passive"))
      (node (ref "J58") (pin "12") (pinfunction "12_12") (pintype "passive"))
      (node (ref "J58") (pin "13") (pinfunction "13_13") (pintype "passive"))
      (node (ref "J58") (pin "14") (pinfunction "14_14") (pintype "passive"))
      (node (ref "J58") (pin "15") (pinfunction "15_15") (pintype "passive"))
      (node (ref "J58") (pin "16") (pinfunction "16_16") (pintype "passive"))
      (node (ref "J58") (pin "17") (pinfunction "17_17") (pintype "passive"))
      (node (ref "J58") (pin "18") (pinfunction "18_18") (pintype "passive"))
      (node (ref "J58") (pin "19") (pinfunction "19_19") (pintype "passive"))
      (node (ref "J58") (pin "2") (pinfunction "2_2") (pintype "passive"))
      (node (ref "J58") (pin "3") (pinfunction "3_3") (pintype "passive"))
      (node (ref "J58") (pin "4") (pinfunction "4_4") (pintype "passive"))
      (node (ref "J58") (pin "5") (pinfunction "5_5") (pintype "passive"))
      (node (ref "J58") (pin "6") (pinfunction "6_6") (pintype "passive"))
      (node (ref "J58") (pin "7") (pinfunction "7_7") (pintype "passive"))
      (node (ref "J58") (pin "8") (pinfunction "8_8") (pintype "passive"))
      (node (ref "J58") (pin "9") (pinfunction "9_9") (pintype "passive"))
    )
    (net (code "30") (name "Net-(J59-Pad1)") (class "Default")
      (node (ref "J59") (pin "1") (pinfunction "1_1") (pintype "passive"))
      (node (ref "J59") (pin "10") (pinfunction "10_10") (pintype "passive"))
      (node (ref "J59") (pin "11") (pinfunction "11_11") (pintype "passive"))
      (node (ref "J59") (pin "12") (pinfunction "12_12") (pintype "passive"))
      (node (ref "J59") (pin "13") (pinfunction "13_13") (pintype "passive"))
      (node (ref "J59") (pin "14") (pinfunction "14_14") (pintype "passive"))
      (node (ref "J59") (pin "15") (pinfunction "15_15") (pintype "passive"))
      (node (ref "J59") (pin "16") (pinfunction "16_16") (pintype "passive"))
      (node (ref "J59") (pin "17") (pinfunction "17_17") (pintype "passive"))
      (node (ref "J59") (pin "18") (pinfunction "18_18") (pintype "passive"))
      (node (ref "J59") (pin "19") (pinfunction "19_19") (pintype "passive"))
      (node (ref "J59") (pin "2") (pinfunction "2_2") (pintype "passive"))
      (node (ref "J59") (pin "3") (pinfunction "3_3") (pintype "passive"))
      (node (ref "J59") (pin "4") (pinfunction "4_4") (pintype "passive"))
      (node (ref "J59") (pin "5") (pinfunction "5_5") (pintype "passive"))
      (node (ref "J59") (pin "6") (pinfunction "6_6") (pintype "passive"))
      (node (ref "J59") (pin "7") (pinfunction "7_7") (pintype "passive"))
      (node (ref "J59") (pin "8") (pinfunction "8_8") (pintype "passive"))
      (node (ref "J59") (pin "9") (pinfunction "9_9") (pintype "passive"))
      (node (ref "J60") (pin "1") (pinfunction "1_1") (pintype "passive"))
      (node (ref "J60") (pin "10") (pinfunction "10_10") (pintype "passive"))
      (node (ref "J60") (pin "11") (pinfunction "11_11") (pintype "passive"))
      (node (ref "J60") (pin "12") (pinfunction "12_12") (pintype "passive"))
      (node (ref "J60") (pin "13") (pinfunction "13_13") (pintype "passive"))
      (node (ref "J60") (pin "14") (pinfunction "14_14") (pintype "passive"))
      (node (ref "J60") (pin "15") (pinfunction "15_15") (pintype "passive"))
      (node (ref "J60") (pin "16") (pinfunction "16_16") (pintype "passive"))
      (node (ref "J60") (pin "17") (pinfunction "17_17") (pintype "passive"))
      (node (ref "J60") (pin "18") (pinfunction "18_18") (pintype "passive"))
      (node (ref "J60") (pin "19") (pinfunction "19_19") (pintype "passive"))
      (node (ref "J60") (pin "2") (pinfunction "2_2") (pintype "passive"))
      (node (ref "J60") (pin "3") (pinfunction "3_3") (pintype "passive"))
      (node (ref "J60") (pin "4") (pinfunction "4_4") (pintype "passive"))
      (node (ref "J60") (pin "5") (pinfunction "5_5") (pintype "passive"))
      (node (ref "J60") (pin "6") (pinfunction "6_6") (pintype "passive"))
      (node (ref "J60") (pin "7") (pinfunction "7_7") (pintype "passive"))
      (node (ref "J60") (pin "8") (pinfunction "8_8") (pintype "passive"))
      (node (ref "J60") (pin "9") (pinfunction "9_9") (pintype "passive"))
    )
    (net (code "31") (name "Net-(J61-Pad1)") (class "Default")
      (node (ref "J61") (pin "1") (pinfunction "1_1") (pintype "passive"))
      (node (ref "J61") (pin "10") (pinfunction "10_10") (pintype "passive"))
      (node (ref "J61") (pin "11") (pinfunction "11_11") (pintype "passive"))
      (node (ref "J61") (pin "12") (pinfunction "12_12") (pintype "passive"))
      (node (ref "J61") (pin "13") (pinfunction "13_13") (pintype "passive"))
      (node (ref "J61") (pin "14") (pinfunction "14_14") (pintype "passive"))
      (node (ref "J61") (pin "15") (pinfunction "15_15") (pintype "passive"))
      (node (ref "J61") (pin "16") (pinfunction "16_16") (pintype "passive"))
      (node (ref "J61") (pin "17") (pinfunction "17_17") (pintype "passive"))
      (node (ref "J61") (pin "18") (pinfunction "18_18") (pintype "passive"))
      (node (ref "J61") (pin "19") (pinfunction "19_19") (pintype "passive"))
      (node (ref "J61") (pin "2") (pinfunction "2_2") (pintype "passive"))
      (node (ref "J61") (pin "3") (pinfunction "3_3") (pintype "passive"))
      (node (ref "J61") (pin "4") (pinfunction "4_4") (pintype "passive"))
      (node (ref "J61") (pin "5") (pinfunction "5_5") (pintype "passive"))
      (node (ref "J61") (pin "6") (pinfunction "6_6") (pintype "passive"))
      (node (ref "J61") (pin "7") (pinfunction "7_7") (pintype "passive"))
      (node (ref "J61") (pin "8") (pinfunction "8_8") (pintype "passive"))
      (node (ref "J61") (pin "9") (pinfunction "9_9") (pintype "passive"))
      (node (ref "J62") (pin "1") (pinfunction "1_1") (pintype "passive"))
      (node (ref "J62") (pin "10") (pinfunction "10_10") (pintype "passive"))
      (node (ref "J62") (pin "11") (pinfunction "11_11") (pintype "passive"))
      (node (ref "J62") (pin "12") (pinfunction "12_12") (pintype "passive"))
      (node (ref "J62") (pin "13") (pinfunction "13_13") (pintype "passive"))
      (node (ref "J62") (pin "14") (pinfunction "14_14") (pintype "passive"))
      (node (ref "J62") (pin "15") (pinfunction "15_15") (pintype "passive"))
      (node (ref "J62") (pin "16") (pinfunction "16_16") (pintype "passive"))
      (node (ref "J62") (pin "17") (pinfunction "17_17") (pintype "passive"))
      (node (ref "J62") (pin "18") (pinfunction "18_18") (pintype "passive"))
      (node (ref "J62") (pin "19") (pinfunction "19_19") (pintype "passive"))
      (node (ref "J62") (pin "2") (pinfunction "2_2") (pintype "passive"))
      (node (ref "J62") (pin "3") (pinfunction "3_3") (pintype "passive"))
      (node (ref "J62") (pin "4") (pinfunction "4_4") (pintype "passive"))
      (node (ref "J62") (pin "5") (pinfunction "5_5") (pintype "passive"))
      (node (ref "J62") (pin "6") (pinfunction "6_6") (pintype "passive"))
      (node (ref "J62") (pin "7") (pinfunction "7_7") (pintype "passive"))
      (node (ref "J62") (pin "8") (pinfunction "8_8") (pintype "passive"))
      (node (ref "J62") (pin "9") (pinfunction "9_9") (pintype "passive"))
    )
    (net (code "32") (name "Net-(J63-Pad1)") (class "Default")
      (node (ref "J63") (pin "1") (pinfunction "1_1") (pintype "passive"))
      (node (ref "J63") (pin "10") (pinfunction "10_10") (pintype "passive"))
      (node (ref "J63") (pin "11") (pinfunction "11_11") (pintype "passive"))
      (node (ref "J63") (pin "12") (pinfunction "12_12") (pintype "passive"))
      (node (ref "J63") (pin "13") (pinfunction "13_13") (pintype "passive"))
      (node (ref "J63") (pin "14") (pinfunction "14_14") (pintype "passive"))
      (node (ref "J63") (pin "15") (pinfunction "15_15") (pintype "passive"))
      (node (ref "J63") (pin "16") (pinfunction "16_16") (pintype "passive"))
      (node (ref "J63") (pin "17") (pinfunction "17_17") (pintype "passive"))
      (node (ref "J63") (pin "18") (pinfunction "18_18") (pintype "passive"))
      (node (ref "J63") (pin "19") (pinfunction "19_19") (pintype "passive"))
      (node (ref "J63") (pin "2") (pinfunction "2_2") (pintype "passive"))
      (node (ref "J63") (pin "3") (pinfunction "3_3") (pintype "passive"))
      (node (ref "J63") (pin "4") (pinfunction "4_4") (pintype "passive"))
      (node (ref "J63") (pin "5") (pinfunction "5_5") (pintype "passive"))
      (node (ref "J63") (pin "6") (pinfunction "6_6") (pintype "passive"))
      (node (ref "J63") (pin "7") (pinfunction "7_7") (pintype "passive"))
      (node (ref "J63") (pin "8") (pinfunction "8_8") (pintype "passive"))
      (node (ref "J63") (pin "9") (pinfunction "9_9") (pintype "passive"))
      (node (ref "J64") (pin "1") (pinfunction "1_1") (pintype "passive"))
      (node (ref "J64") (pin "10") (pinfunction "10_10") (pintype "passive"))
      (node (ref "J64") (pin "11") (pinfunction "11_11") (pintype "passive"))
      (node (ref "J64") (pin "12") (pinfunction "12_12") (pintype "passive"))
      (node (ref "J64") (pin "13") (pinfunction "13_13") (pintype "passive"))
      (node (ref "J64") (pin "14") (pinfunction "14_14") (pintype "passive"))
      (node (ref "J64") (pin "15") (pinfunction "15_15") (pintype "passive"))
      (node (ref "J64") (pin "16") (pinfunction "16_16") (pintype "passive"))
      (node (ref "J64") (pin "17") (pinfunction "17_17") (pintype "passive"))
      (node (ref "J64") (pin "18") (pinfunction "18_18") (pintype "passive"))
      (node (ref "J64") (pin "19") (pinfunction "19_19") (pintype "passive"))
      (node (ref "J64") (pin "2") (pinfunction "2_2") (pintype "passive"))
      (node (ref "J64") (pin "3") (pinfunction "3_3") (pintype "passive"))
      (node (ref "J64") (pin "4") (pinfunction "4_4") (pintype "passive"))
      (node (ref "J64") (pin "5") (pinfunction "5_5") (pintype "passive"))
      (node (ref "J64") (pin "6") (pinfunction "6_6") (pintype "passive"))
      (node (ref "J64") (pin "7") (pinfunction "7_7") (pintype "passive"))
      (node (ref "J64") (pin "8") (pinfunction "8_8") (pintype "passive"))
      (node (ref "J64") (pin "9") (pinfunction "9_9") (pintype "passive"))
    )
    (net (code "33") (name "Net-(J65-Pad1)") (class "Default")
      (node (ref "J65") (pin "1") (pinfunction "1_1") (pintype "passive"))
      (node (ref "J65") (pin "10") (pinfunction "10_10") (pintype "passive"))
      (node (ref "J65") (pin "11") (pinfunction "11_11") (pintype "passive"))
      (node (ref "J65") (pin "12") (pinfunction "12_12") (pintype "passive"))
      (node (ref "J65") (pin "13") (pinfunction "13_13") (pintype "passive"))
      (node (ref "J65") (pin "14") (pinfunction "14_14") (pintype "passive"))
      (node (ref "J65") (pin "15") (pinfunction "15_15") (pintype "passive"))
      (node (ref "J65") (pin "2") (pinfunction "2_2") (pintype "passive"))
      (node (ref "J65") (pin "3") (pinfunction "3_3") (pintype "passive"))
      (node (ref "J65") (pin "4") (pinfunction "4_4") (pintype "passive"))
      (node (ref "J65") (pin "5") (pinfunction "5_5") (pintype "passive"))
      (node (ref "J65") (pin "6") (pinfunction "6_6") (pintype "passive"))
      (node (ref "J65") (pin "7") (pinfunction "7_7") (pintype "passive"))
      (node (ref "J65") (pin "8") (pinfunction "8_8") (pintype "passive"))
      (node (ref "J65") (pin "9") (pinfunction "9_9") (pintype "passive"))
      (node (ref "J66") (pin "1") (pinfunction "1_1") (pintype "passive"))
      (node (ref "J66") (pin "10") (pinfunction "10_10") (pintype "passive"))
      (node (ref "J66") (pin "11") (pinfunction "11_11") (pintype "passive"))
      (node (ref "J66") (pin "12") (pinfunction "12_12") (pintype "passive"))
      (node (ref "J66") (pin "13") (pinfunction "13_13") (pintype "passive"))
      (node (ref "J66") (pin "14") (pinfunction "14_14") (pintype "passive"))
      (node (ref "J66") (pin "15") (pinfunction "15_15") (pintype "passive"))
      (node (ref "J66") (pin "2") (pinfunction "2_2") (pintype "passive"))
      (node (ref "J66") (pin "3") (pinfunction "3_3") (pintype "passive"))
      (node (ref "J66") (pin "4") (pinfunction "4_4") (pintype "passive"))
      (node (ref "J66") (pin "5") (pinfunction "5_5") (pintype "passive"))
      (node (ref "J66") (pin "6") (pinfunction "6_6") (pintype "passive"))
      (node (ref "J66") (pin "7") (pinfunction "7_7") (pintype "passive"))
      (node (ref "J66") (pin "8") (pinfunction "8_8") (pintype "passive"))
      (node (ref "J66") (pin "9") (pinfunction "9_9") (pintype "passive"))
    )
    (net (code "34") (name "Net-(J67-Pad1)") (class "Default")
      (node (ref "J67") (pin "1") (pinfunction "1_1") (pintype "passive"))
      (node (ref "J67") (pin "10") (pinfunction "10_10") (pintype "passive"))
      (node (ref "J67") (pin "11") (pinfunction "11_11") (pintype "passive"))
      (node (ref "J67") (pin "12") (pinfunction "12_12") (pintype "passive"))
      (node (ref "J67") (pin "13") (pinfunction "13_13") (pintype "passive"))
      (node (ref "J67") (pin "14") (pinfunction "14_14") (pintype "passive"))
      (node (ref "J67") (pin "15") (pinfunction "15_15") (pintype "passive"))
      (node (ref "J67") (pin "2") (pinfunction "2_2") (pintype "passive"))
      (node (ref "J67") (pin "3") (pinfunction "3_3") (pintype "passive"))
      (node (ref "J67") (pin "4") (pinfunction "4_4") (pintype "passive"))
      (node (ref "J67") (pin "5") (pinfunction "5_5") (pintype "passive"))
      (node (ref "J67") (pin "6") (pinfunction "6_6") (pintype "passive"))
      (node (ref "J67") (pin "7") (pinfunction "7_7") (pintype "passive"))
      (node (ref "J67") (pin "8") (pinfunction "8_8") (pintype "passive"))
      (node (ref "J67") (pin "9") (pinfunction "9_9") (pintype "passive"))
      (node (ref "J68") (pin "1") (pinfunction "1_1") (pintype "passive"))
      (node (ref "J68") (pin "10") (pinfunction "10_10") (pintype "passive"))
      (node (ref "J68") (pin "11") (pinfunction "11_11") (pintype "passive"))
      (node (ref "J68") (pin "12") (pinfunction "12_12") (pintype "passive"))
      (node (ref "J68") (pin "13") (pinfunction "13_13") (pintype "passive"))
      (node (ref "J68") (pin "14") (pinfunction "14_14") (pintype "passive"))
      (node (ref "J68") (pin "15") (pinfunction "15_15") (pintype "passive"))
      (node (ref "J68") (pin "2") (pinfunction "2_2") (pintype "passive"))
      (node (ref "J68") (pin "3") (pinfunction "3_3") (pintype "passive"))
      (node (ref "J68") (pin "4") (pinfunction "4_4") (pintype "passive"))
      (node (ref "J68") (pin "5") (pinfunction "5_5") (pintype "passive"))
      (node (ref "J68") (pin "6") (pinfunction "6_6") (pintype "passive"))
      (node (ref "J68") (pin "7") (pinfunction "7_7") (pintype "passive"))
      (node (ref "J68") (pin "8") (pinfunction "8_8") (pintype "passive"))
      (node (ref "J68") (pin "9") (pinfunction "9_9") (pintype "passive"))
    )
    (net (code "35") (name "Net-(J69-Pad1)") (class "Default")
      (node (ref "J69") (pin "1") (pinfunction "1_1") (pintype "passive"))
      (node (ref "J69") (pin "10") (pinfunction "10_10") (pintype "passive"))
      (node (ref "J69") (pin "11") (pinfunction "11_11") (pintype "passive"))
      (node (ref "J69") (pin "12") (pinfunction "12_12") (pintype "passive"))
      (node (ref "J69") (pin "13") (pinfunction "13_13") (pintype "passive"))
      (node (ref "J69") (pin "14") (pinfunction "14_14") (pintype "passive"))
      (node (ref "J69") (pin "15") (pinfunction "15_15") (pintype "passive"))
      (node (ref "J69") (pin "2") (pinfunction "2_2") (pintype "passive"))
      (node (ref "J69") (pin "3") (pinfunction "3_3") (pintype "passive"))
      (node (ref "J69") (pin "4") (pinfunction "4_4") (pintype "passive"))
      (node (ref "J69") (pin "5") (pinfunction "5_5") (pintype "passive"))
      (node (ref "J69") (pin "6") (pinfunction "6_6") (pintype "passive"))
      (node (ref "J69") (pin "7") (pinfunction "7_7") (pintype "passive"))
      (node (ref "J69") (pin "8") (pinfunction "8_8") (pintype "passive"))
      (node (ref "J69") (pin "9") (pinfunction "9_9") (pintype "passive"))
      (node (ref "J70") (pin "1") (pinfunction "1_1") (pintype "passive"))
      (node (ref "J70") (pin "10") (pinfunction "10_10") (pintype "passive"))
      (node (ref "J70") (pin "11") (pinfunction "11_11") (pintype "passive"))
      (node (ref "J70") (pin "12") (pinfunction "12_12") (pintype "passive"))
      (node (ref "J70") (pin "13") (pinfunction "13_13") (pintype "passive"))
      (node (ref "J70") (pin "14") (pinfunction "14_14") (pintype "passive"))
      (node (ref "J70") (pin "15") (pinfunction "15_15") (pintype "passive"))
      (node (ref "J70") (pin "2") (pinfunction "2_2") (pintype "passive"))
      (node (ref "J70") (pin "3") (pinfunction "3_3") (pintype "passive"))
      (node (ref "J70") (pin "4") (pinfunction "4_4") (pintype "passive"))
      (node (ref "J70") (pin "5") (pinfunction "5_5") (pintype "passive"))
      (node (ref "J70") (pin "6") (pinfunction "6_6") (pintype "passive"))
      (node (ref "J70") (pin "7") (pinfunction "7_7") (pintype "passive"))
      (node (ref "J70") (pin "8") (pinfunction "8_8") (pintype "passive"))
      (node (ref "J70") (pin "9") (pinfunction "9_9") (pintype "passive"))
    )
    (net (code "36") (name "Net-(J71-Pad1)") (class "Default")
      (node (ref "J71") (pin "1") (pinfunction "1_1") (pintype "passive"))
      (node (ref "J71") (pin "10") (pinfunction "10_10") (pintype "passive"))
      (node (ref "J71") (pin "11") (pinfunction "11_11") (pintype "passive"))
      (node (ref "J71") (pin "12") (pinfunction "12_12") (pintype "passive"))
      (node (ref "J71") (pin "13") (pinfunction "13_13") (pintype "passive"))
      (node (ref "J71") (pin "14") (pinfunction "14_14") (pintype "passive"))
      (node (ref "J71") (pin "15") (pinfunction "15_15") (pintype "passive"))
      (node (ref "J71") (pin "2") (pinfunction "2_2") (pintype "passive"))
      (node (ref "J71") (pin "3") (pinfunction "3_3") (pintype "passive"))
      (node (ref "J71") (pin "4") (pinfunction "4_4") (pintype "passive"))
      (node (ref "J71") (pin "5") (pinfunction "5_5") (pintype "passive"))
      (node (ref "J71") (pin "6") (pinfunction "6_6") (pintype "passive"))
      (node (ref "J71") (pin "7") (pinfunction "7_7") (pintype "passive"))
      (node (ref "J71") (pin "8") (pinfunction "8_8") (pintype "passive"))
      (node (ref "J71") (pin "9") (pinfunction "9_9") (pintype "passive"))
      (node (ref "J72") (pin "1") (pinfunction "1_1") (pintype "passive"))
      (node (ref "J72") (pin "10") (pinfunction "10_10") (pintype "passive"))
      (node (ref "J72") (pin "11") (pinfunction "11_11") (pintype "passive"))
      (node (ref "J72") (pin "12") (pinfunction "12_12") (pintype "passive"))
      (node (ref "J72") (pin "13") (pinfunction "13_13") (pintype "passive"))
      (node (ref "J72") (pin "14") (pinfunction "14_14") (pintype "passive"))
      (node (ref "J72") (pin "15") (pinfunction "15_15") (pintype "passive"))
      (node (ref "J72") (pin "2") (pinfunction "2_2") (pintype "passive"))
      (node (ref "J72") (pin "3") (pinfunction "3_3") (pintype "passive"))
      (node (ref "J72") (pin "4") (pinfunction "4_4") (pintype "passive"))
      (node (ref "J72") (pin "5") (pinfunction "5_5") (pintype "passive"))
      (node (ref "J72") (pin "6") (pinfunction "6_6") (pintype "passive"))
      (node (ref "J72") (pin "7") (pinfunction "7_7") (pintype "passive"))
      (node (ref "J72") (pin "8") (pinfunction "8_8") (pintype "passive"))
      (node (ref "J72") (pin "9") (pinfunction "9_9") (pintype "passive"))
    )
  )
)
